# ProPrj_ESP32-S3.net
KiCad netlist of a schematic drawn in EasyEDA Pro
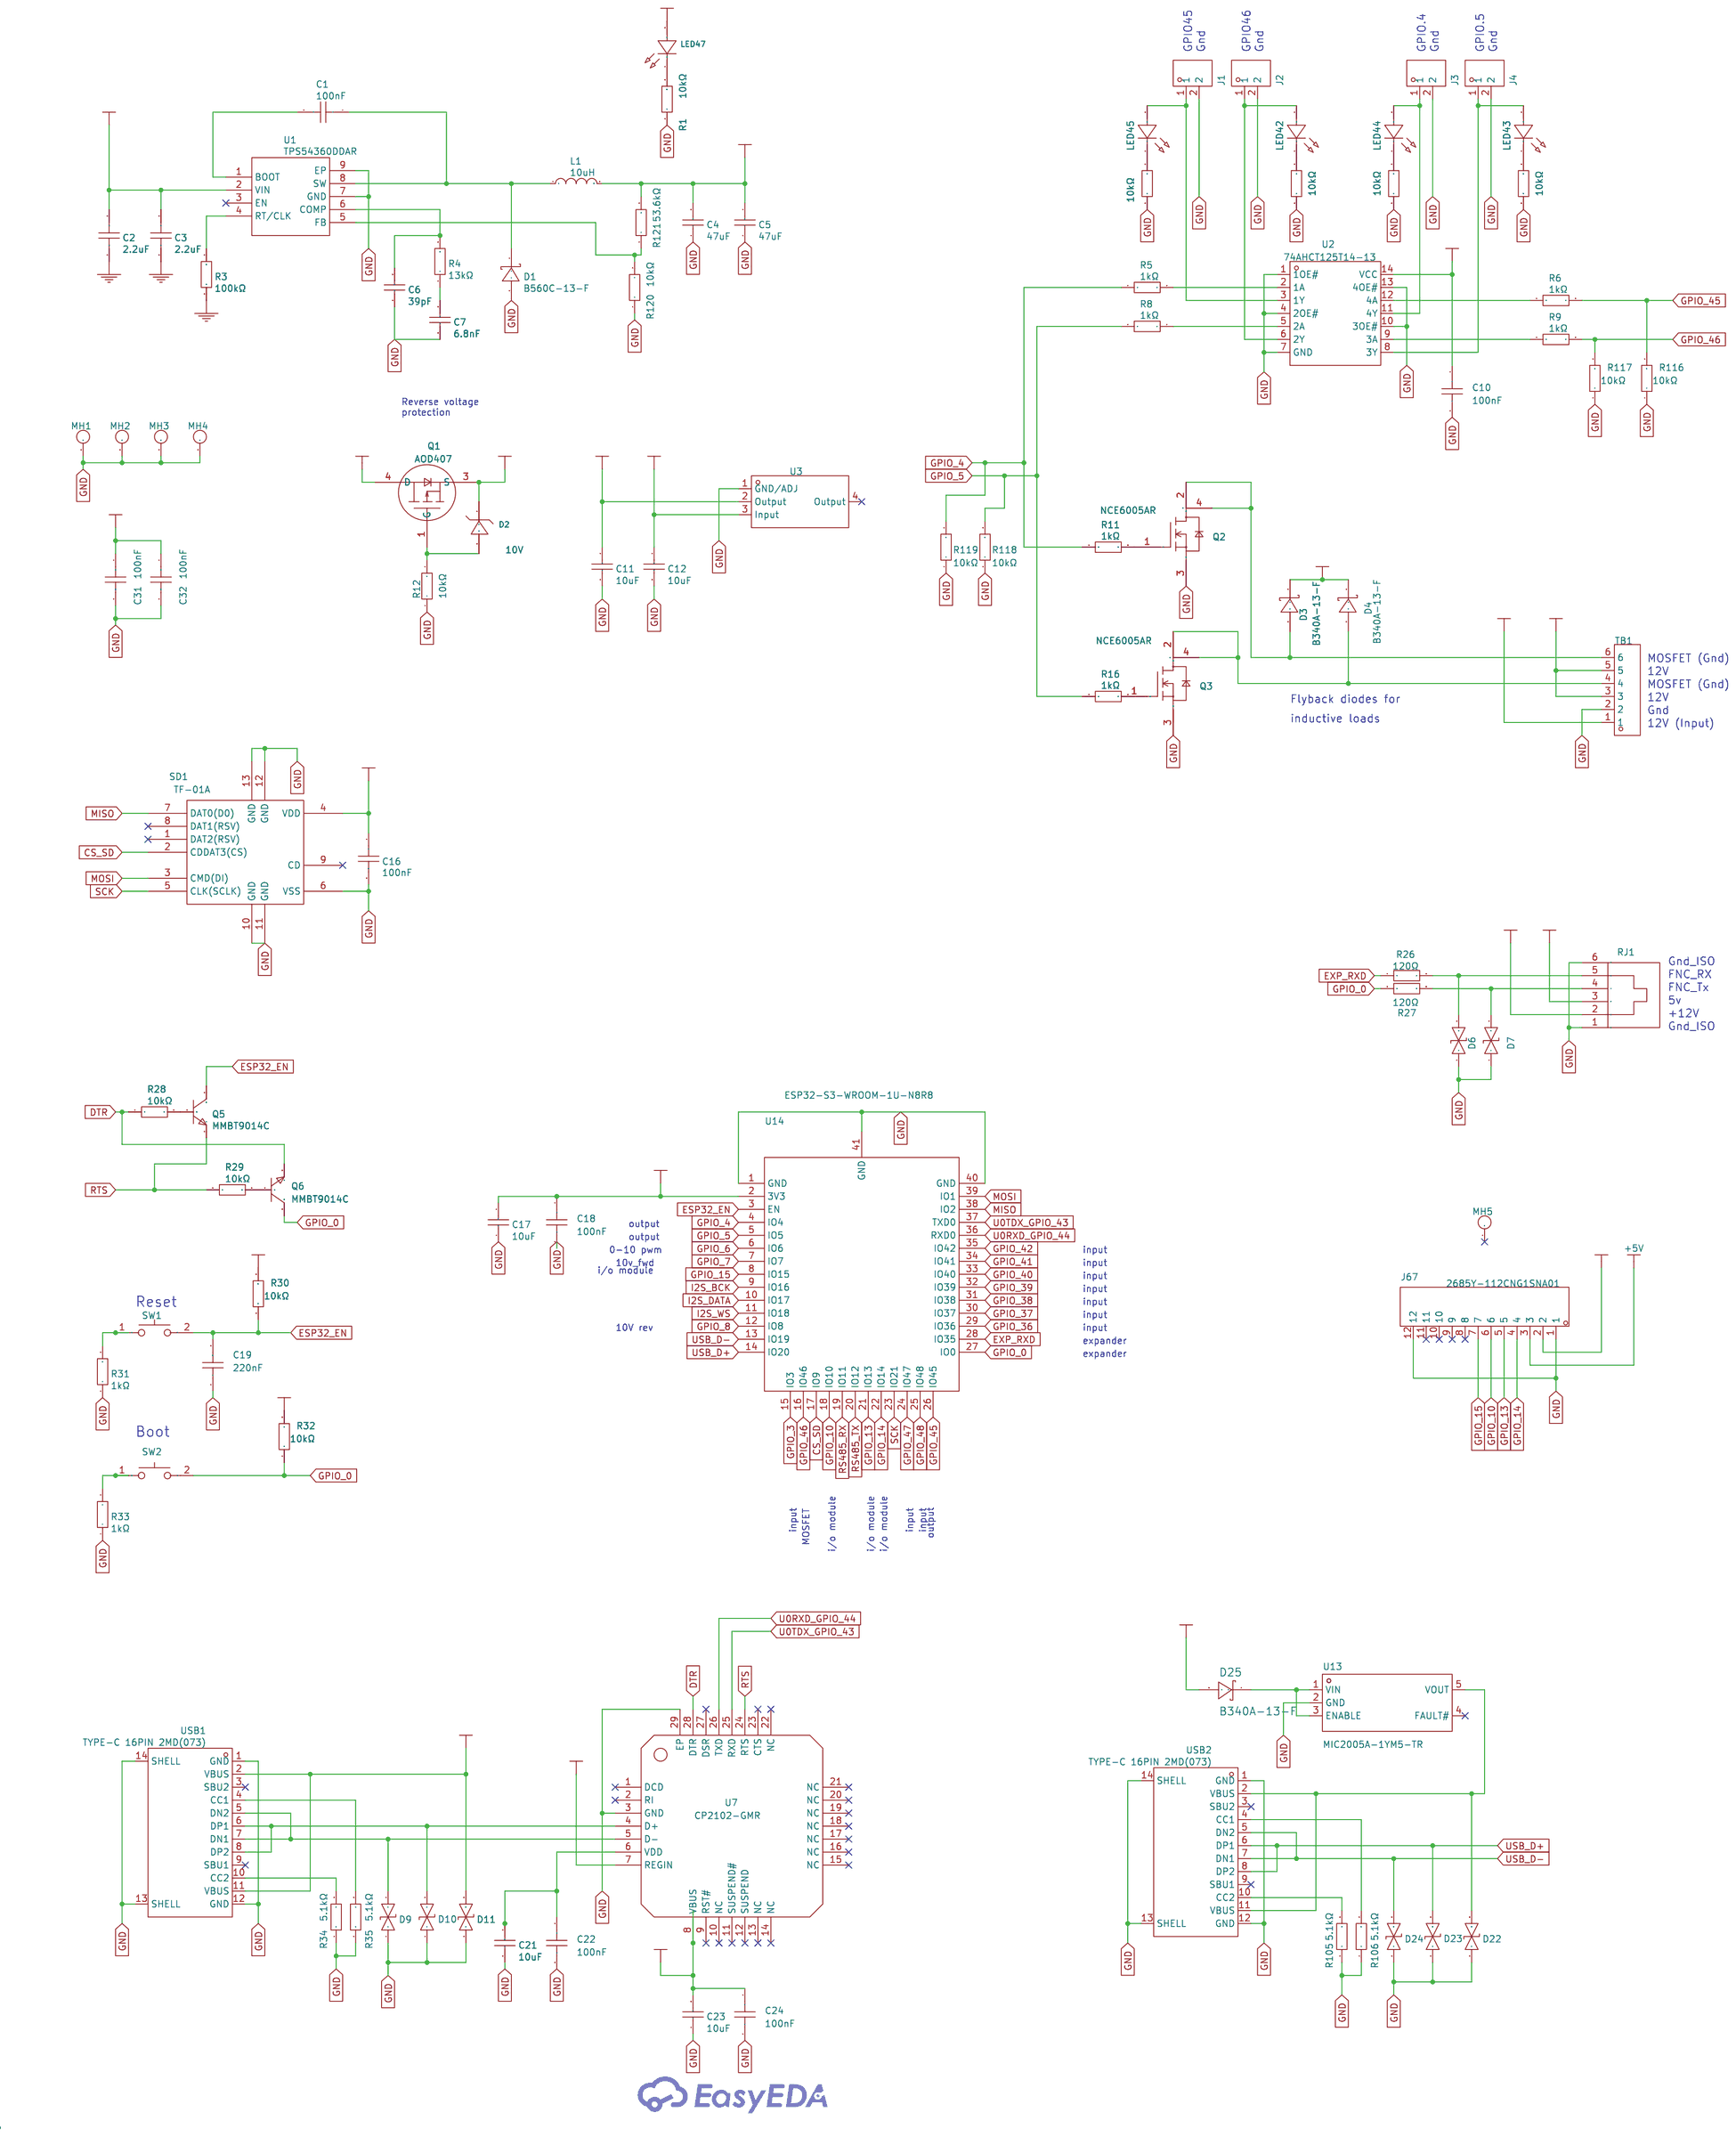
[diagram p0: P1]
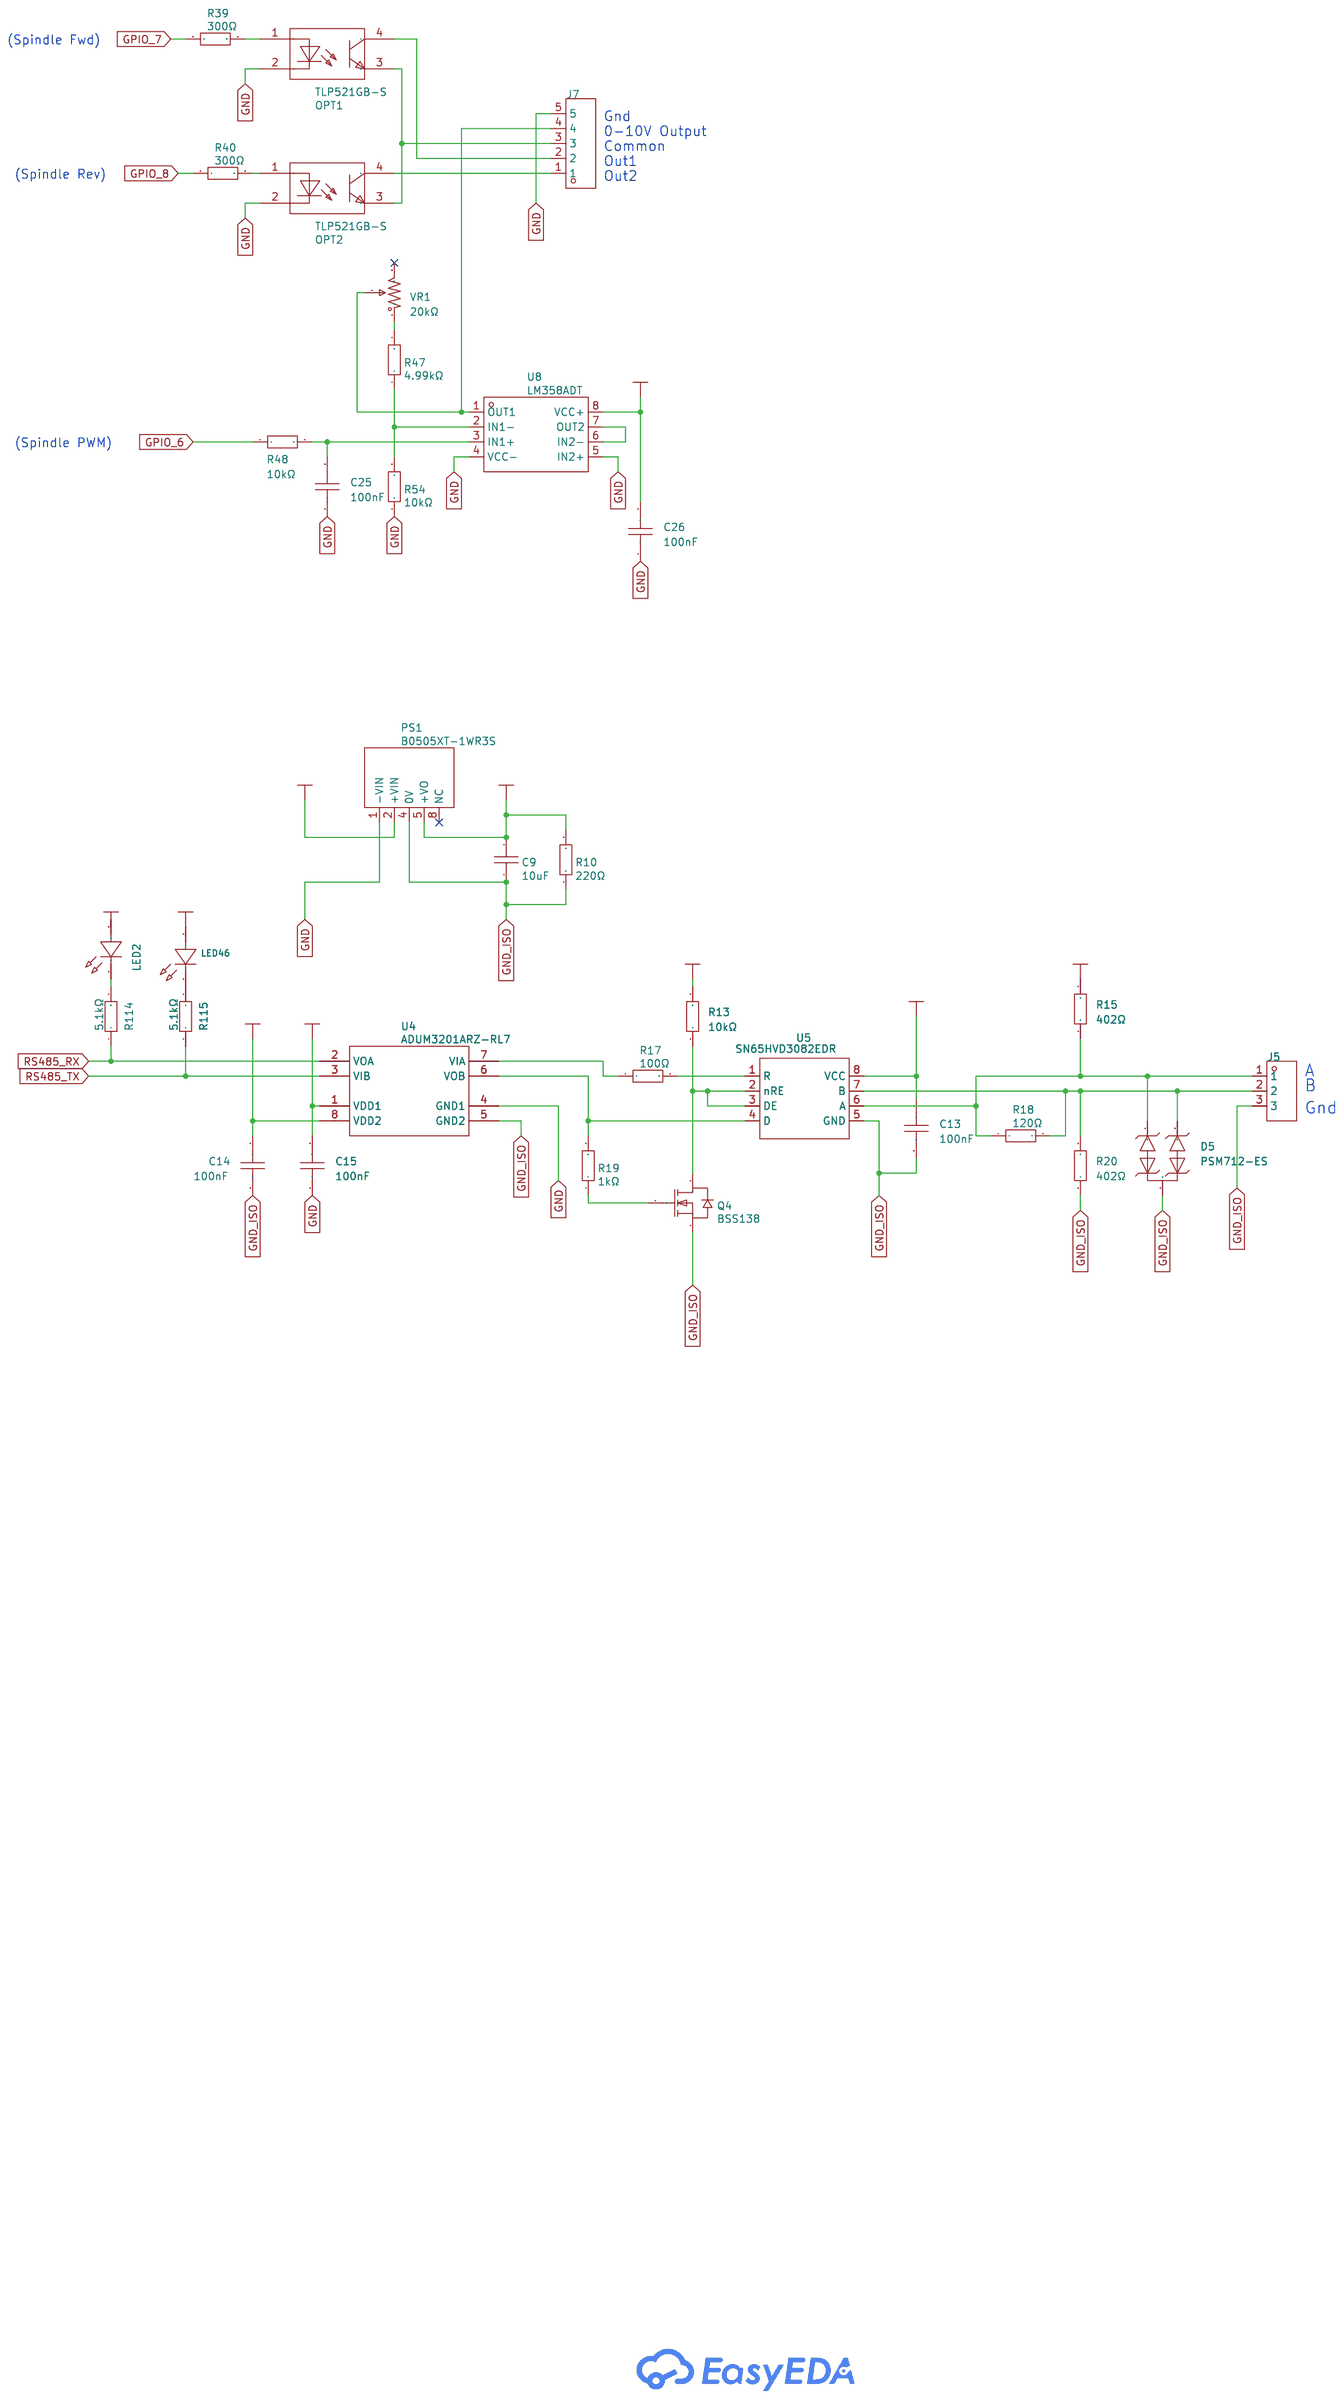
[diagram p1: P2]
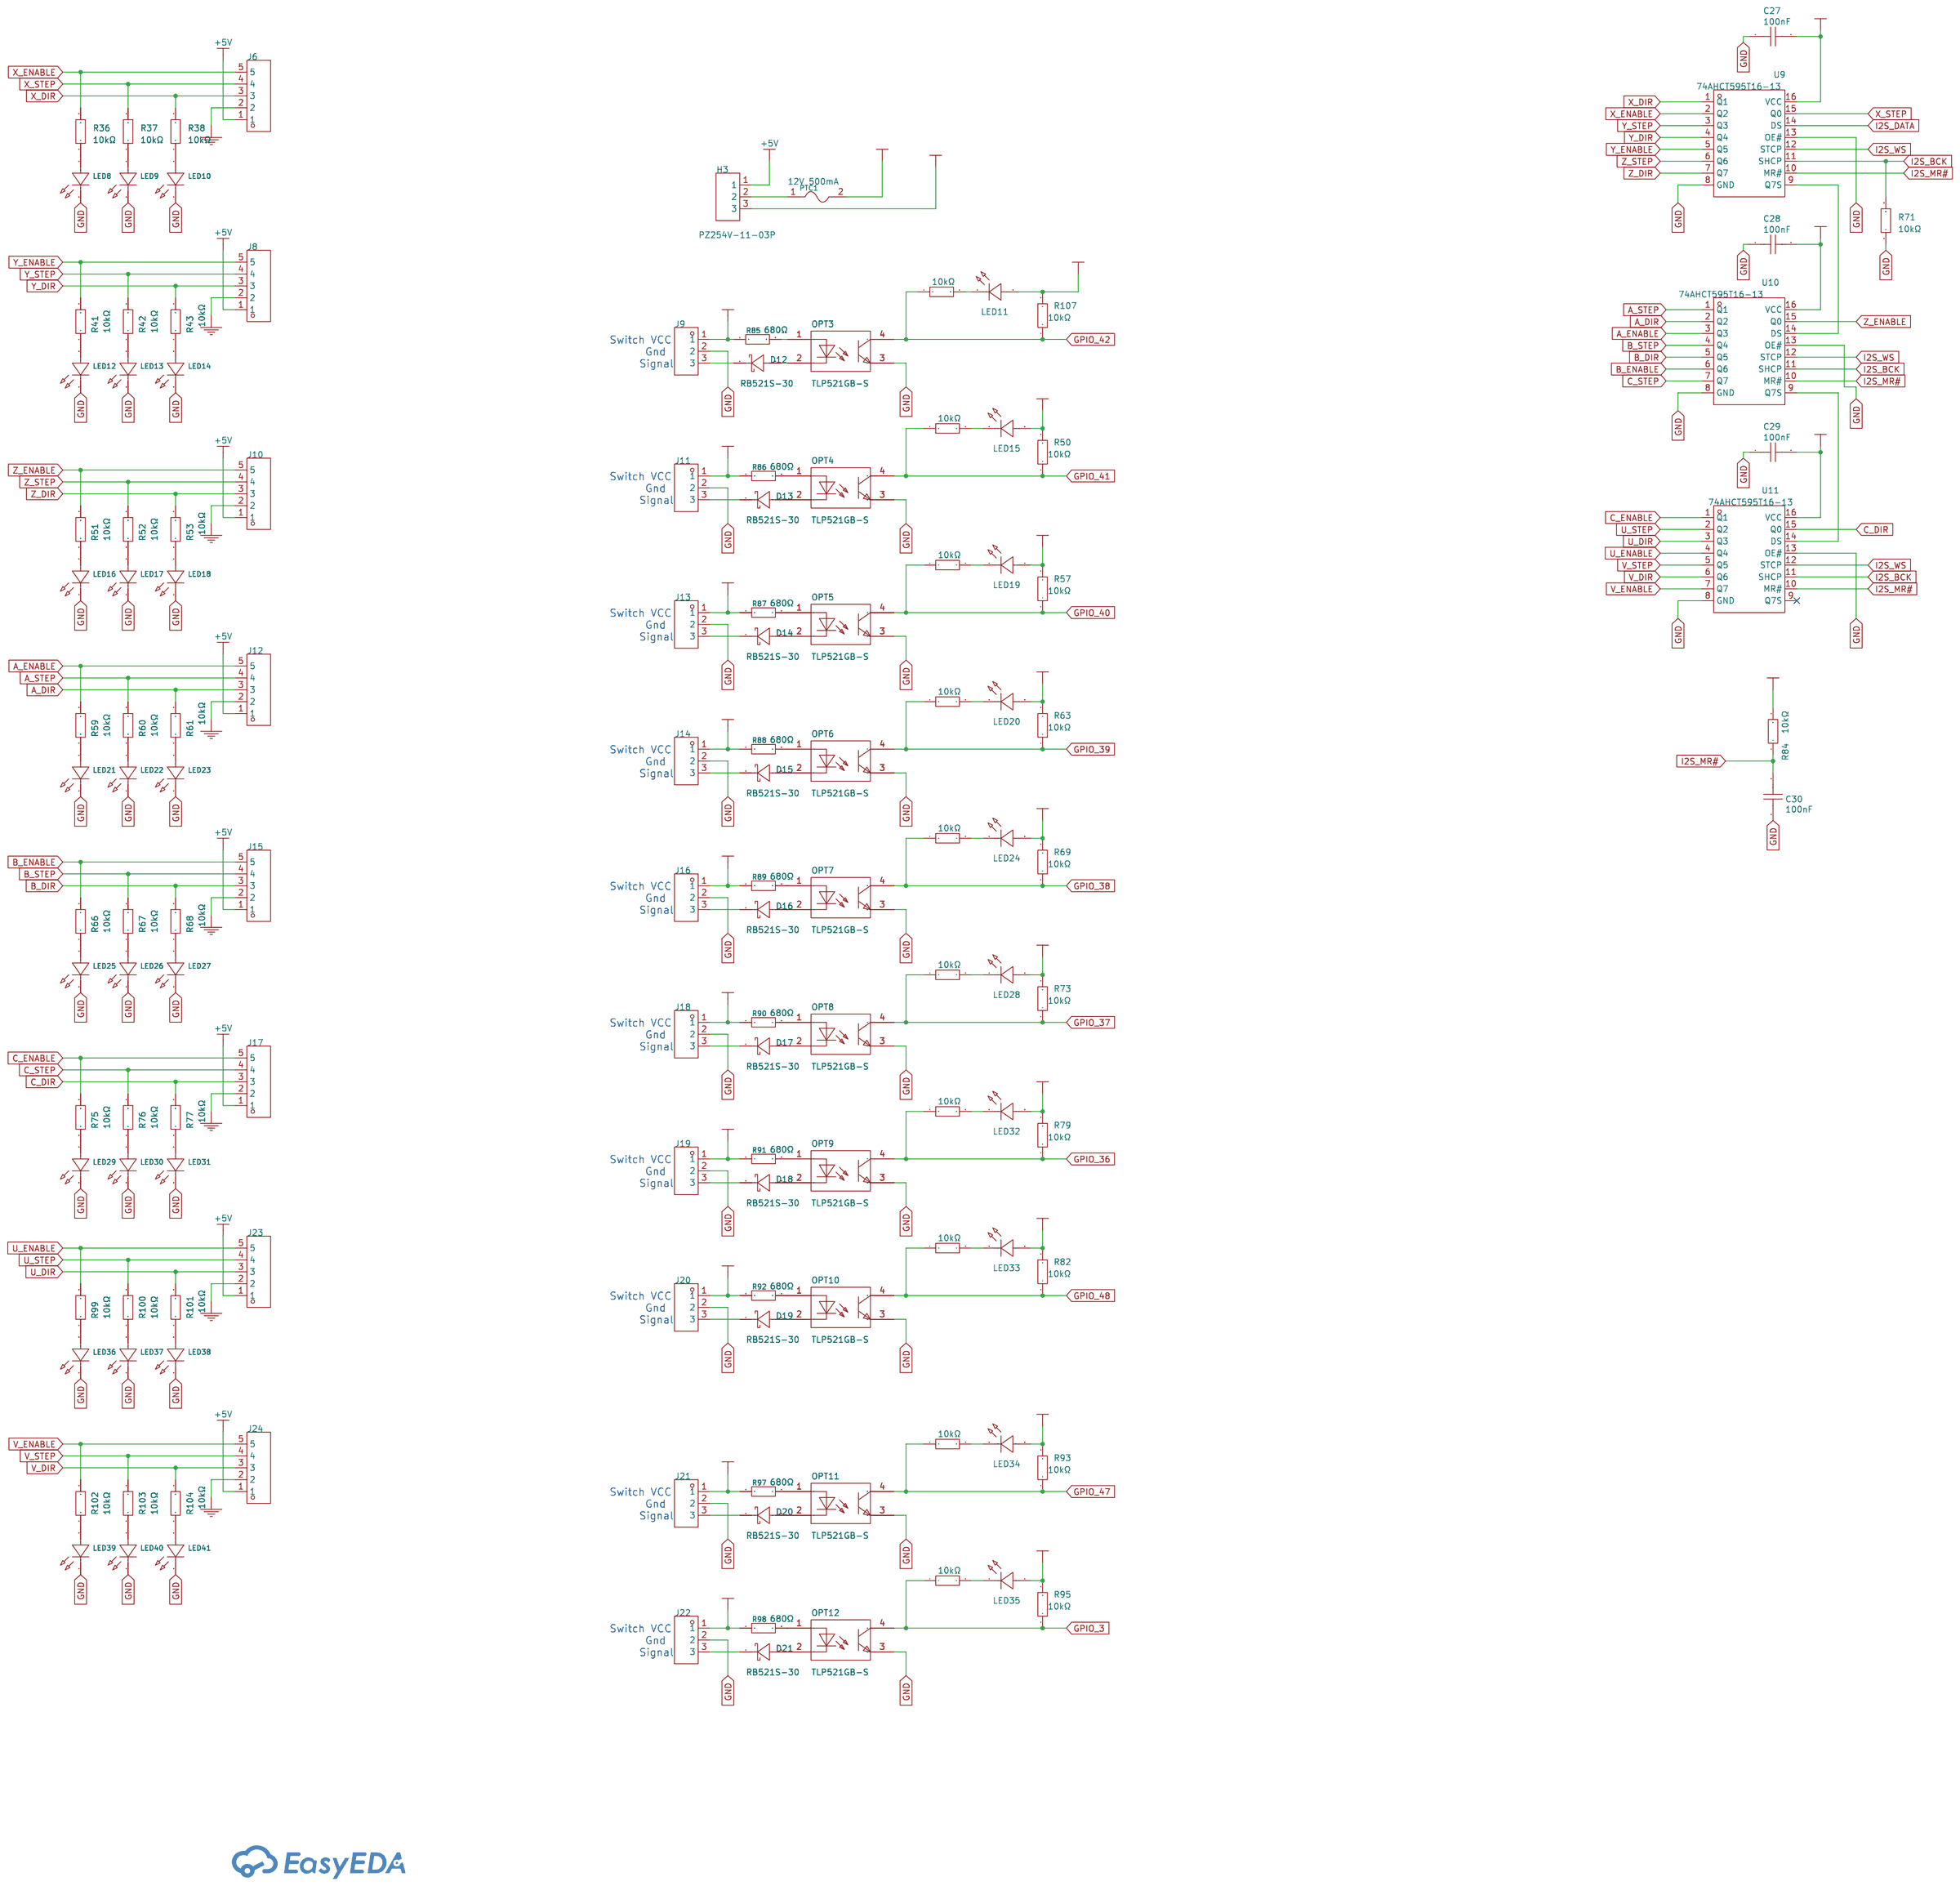
[diagram p2: P3]

(export (version "E")
  (design (tool "Eeschema 10.0.6"))
  (components
    (comp (ref "C1")
      (value "100nF")
      (footprint "easyedapro:C0402")
      (fields (field (name "Manufacturer Part") "GCM155R71C104KA55D") (field (name "Manufacturer") "MuRata"))
      (libsource (lib "easyedapro") (part "100nF"))
    )
    (comp (ref "C2")
      (value "2.2uF")
      (footprint "easyedapro:C0805")
      (fields
        (field (name "Manufacturer Part") "CS2012X5R225K500NRE")
        (field (name "Manufacturer") "SAMWHA(三和)")
      )
      (libsource (lib "easyedapro") (part "2.2uF"))
    )
    (comp (ref "C3")
      (value "2.2uF")
      (footprint "easyedapro:C0805")
      (fields
        (field (name "Manufacturer Part") "CS2012X5R225K500NRE")
        (field (name "Manufacturer") "SAMWHA(三和)")
      )
      (libsource (lib "easyedapro") (part "2.2uF"))
    )
    (comp (ref "C4")
      (value "47uF")
      (footprint "easyedapro:C0805")
      (fields (field (name "Manufacturer Part") "CL21A476MQYNNNE") (field (name "Manufacturer") "SAMSUNG"))
      (libsource (lib "easyedapro") (part "47uF"))
    )
    (comp (ref "C5")
      (value "47uF")
      (footprint "easyedapro:C0805")
      (fields (field (name "Manufacturer Part") "CL21A476MQYNNNE") (field (name "Manufacturer") "SAMSUNG"))
      (libsource (lib "easyedapro") (part "47uF"))
    )
    (comp (ref "C6")
      (value "39pF")
      (footprint "easyedapro:C0402")
      (fields (field (name "Manufacturer Part") "CC0402JRNPO9BN390") (field (name "Manufacturer") "YAGEO"))
      (libsource (lib "easyedapro") (part "39pF"))
    )
    (comp (ref "C7")
      (value "6.8nF")
      (footprint "easyedapro:C0402")
      (fields (field (name "Manufacturer Part") "0402B682K500NT") (field (name "Manufacturer") "FH"))
      (libsource (lib "easyedapro") (part "6.8nF"))
    )
    (comp (ref "C10")
      (value "100nF")
      (footprint "easyedapro:C0402")
      (fields (field (name "Manufacturer Part") "GCM155R71C104KA55D") (field (name "Manufacturer") "MuRata"))
      (libsource (lib "easyedapro") (part "100nF"))
    )
    (comp (ref "C11")
      (value "10uF")
      (footprint "easyedapro:C0805")
      (fields (field (name "Manufacturer Part") "CL21A106KAYNNNE") (field (name "Manufacturer") "SAMSUNG"))
      (libsource (lib "easyedapro") (part "10uF"))
    )
    (comp (ref "C12")
      (value "10uF")
      (footprint "easyedapro:C0805")
      (fields (field (name "Manufacturer Part") "CL21A106KAYNNNE") (field (name "Manufacturer") "SAMSUNG"))
      (libsource (lib "easyedapro") (part "10uF"))
    )
    (comp (ref "C16")
      (value "100nF")
      (footprint "easyedapro:C0402")
      (fields (field (name "Manufacturer Part") "GCM155R71C104KA55D") (field (name "Manufacturer") "MuRata"))
      (libsource (lib "easyedapro") (part "100nF"))
    )
    (comp (ref "C17")
      (value "10uF")
      (footprint "easyedapro:C0805")
      (fields (field (name "Manufacturer Part") "CL21A106KAYNNNE") (field (name "Manufacturer") "SAMSUNG"))
      (libsource (lib "easyedapro") (part "10uF"))
    )
    (comp (ref "C18")
      (value "100nF")
      (footprint "easyedapro:C0402")
      (fields (field (name "Manufacturer Part") "GCM155R71C104KA55D") (field (name "Manufacturer") "MuRata"))
      (libsource (lib "easyedapro") (part "100nF"))
    )
    (comp (ref "C19")
      (value "220nF")
      (footprint "easyedapro:C0402")
      (description "Capacitance:220nF Tolerance:±10% Tolerance:±10% Voltage Rating:16V Temperature Coefficient:X7R")
      (fields (field (name "Manufacturer Part") "0402B224K160NT") (field (name "Manufacturer") "FH(风华)"))
      (libsource (lib "easyedapro") (part "0402B224K160NT"))
    )
    (comp (ref "C21")
      (value "10uF")
      (footprint "easyedapro:C0805")
      (fields (field (name "Manufacturer Part") "CL21A106KAYNNNE") (field (name "Manufacturer") "SAMSUNG"))
      (libsource (lib "easyedapro") (part "10uF"))
    )
    (comp (ref "C22")
      (value "100nF")
      (footprint "easyedapro:C0402")
      (fields (field (name "Manufacturer Part") "GCM155R71C104KA55D") (field (name "Manufacturer") "MuRata"))
      (libsource (lib "easyedapro") (part "100nF"))
    )
    (comp (ref "C23")
      (value "10uF")
      (footprint "easyedapro:C0805")
      (fields (field (name "Manufacturer Part") "CL21A106KAYNNNE") (field (name "Manufacturer") "SAMSUNG"))
      (libsource (lib "easyedapro") (part "10uF"))
    )
    (comp (ref "C24")
      (value "100nF")
      (footprint "easyedapro:C0402")
      (fields (field (name "Manufacturer Part") "GCM155R71C104KA55D") (field (name "Manufacturer") "MuRata"))
      (libsource (lib "easyedapro") (part "100nF"))
    )
    (comp (ref "C31")
      (value "100nF")
      (footprint "easyedapro:C0402")
      (fields (field (name "Manufacturer Part") "GCM155R71C104KA55D") (field (name "Manufacturer") "MuRata"))
      (libsource (lib "easyedapro") (part "100nF"))
    )
    (comp (ref "C32")
      (value "100nF")
      (footprint "easyedapro:C0402")
      (fields (field (name "Manufacturer Part") "GCM155R71C104KA55D") (field (name "Manufacturer") "MuRata"))
      (libsource (lib "easyedapro") (part "100nF"))
    )
    (comp (ref "D1")
      (value "B560C-13-F")
      (footprint "easyedapro:SMC_L7.1-W6.2-LS8.1-RD")
      (fields (field (name "Manufacturer") "DIODES(美台)"))
      (libsource (lib "easyedapro") (part "B560C-13-F"))
    )
    (comp (ref "D2")
      (value "10V")
      (footprint "easyedapro:SOD-123_L2.8-W1.8-LS3.7-RD")
      (fields (field (name "Manufacturer Part") "BZT52C10") (field (name "Manufacturer") "MDD"))
      (libsource (lib "easyedapro") (part "BZT52C10_C173431"))
    )
    (comp (ref "D3")
      (value "B340A-13-F")
      (footprint "easyedapro:SMA_L4.4-W2.6-LS5.0-RD")
      (fields (field (name "Manufacturer") "DIODES(美台)"))
      (libsource (lib "easyedapro") (part "B340A-13-F"))
    )
    (comp (ref "D4")
      (value "B340A-13-F")
      (footprint "easyedapro:SMA_L4.4-W2.6-LS5.0-RD")
      (fields (field (name "Manufacturer") "DIODES(美台)"))
      (libsource (lib "easyedapro") (part "B340A-13-F"))
    )
    (comp (ref "D6")
      (value "SD03C_C502532")
      (footprint "easyedapro:SOD-323_L1.8-W1.3-LS2.5-BI")
      (fields
        (field (name "Manufacturer Part") "SD03C")
        (field (name "Manufacturer") "MDD")
        (field (name "Contributor") "LCSC")
      )
      (libsource (lib "easyedapro") (part "SD03C_C502532"))
    )
    (comp (ref "D7")
      (value "SD03C_C502532")
      (footprint "easyedapro:SOD-323_L1.8-W1.3-LS2.5-BI")
      (fields
        (field (name "Manufacturer Part") "SD03C")
        (field (name "Manufacturer") "MDD")
        (field (name "Contributor") "LCSC")
      )
      (libsource (lib "easyedapro") (part "SD03C_C502532"))
    )
    (comp (ref "D9")
      (value "LESD5D5.0CT1G")
      (footprint "easyedapro:SOD-523_L1.2-W0.8-LS1.6-BI")
      (fields (field (name "Manufacturer") "Leshan Radio"))
      (libsource (lib "easyedapro") (part "LESD5D5.0CT1G"))
    )
    (comp (ref "D10")
      (value "LESD5D5.0CT1G")
      (footprint "easyedapro:SOD-523_L1.2-W0.8-LS1.6-BI")
      (fields (field (name "Manufacturer") "Leshan Radio"))
      (libsource (lib "easyedapro") (part "LESD5D5.0CT1G"))
    )
    (comp (ref "D11")
      (value "LESD5D5.0CT1G")
      (footprint "easyedapro:SOD-523_L1.2-W0.8-LS1.6-BI")
      (fields (field (name "Manufacturer") "Leshan Radio"))
      (libsource (lib "easyedapro") (part "LESD5D5.0CT1G"))
    )
    (comp (ref "D22")
      (value "LESD5D5.0CT1G")
      (footprint "easyedapro:SOD-523_L1.2-W0.8-LS1.6-BI")
      (fields (field (name "Manufacturer") "Leshan Radio"))
      (libsource (lib "easyedapro") (part "LESD5D5.0CT1G"))
    )
    (comp (ref "D23")
      (value "LESD5D5.0CT1G")
      (footprint "easyedapro:SOD-523_L1.2-W0.8-LS1.6-BI")
      (fields (field (name "Manufacturer") "Leshan Radio"))
      (libsource (lib "easyedapro") (part "LESD5D5.0CT1G"))
    )
    (comp (ref "D24")
      (value "LESD5D5.0CT1G")
      (footprint "easyedapro:SOD-523_L1.2-W0.8-LS1.6-BI")
      (fields (field (name "Manufacturer") "Leshan Radio"))
      (libsource (lib "easyedapro") (part "LESD5D5.0CT1G"))
    )
    (comp (ref "D25")
      (value "B340A-13-F")
      (footprint "easyedapro:SMA_L4.4-W2.6-LS5.0-RD")
      (fields (field (name "Manufacturer") "DIODES(美台)"))
      (libsource (lib "easyedapro") (part "B340A-13-F"))
    )
    (comp (ref "J1")
      (value "ZX-XH2.54-2PZZ-R")
      (footprint "easyedapro:CONN-TH_XH2.54-2P")
      (fields (field (name "Manufacturer") "Megastar(兆星)"))
      (libsource (lib "easyedapro") (part "ZX-XH2.54-2PZZ-R"))
    )
    (comp (ref "J2")
      (value "ZX-XH2.54-2PZZ-R")
      (footprint "easyedapro:CONN-TH_XH2.54-2P")
      (fields (field (name "Manufacturer") "Megastar(兆星)"))
      (libsource (lib "easyedapro") (part "ZX-XH2.54-2PZZ-R"))
    )
    (comp (ref "J3")
      (value "ZX-XH2.54-2PZZ-R")
      (footprint "easyedapro:CONN-TH_XH2.54-2P")
      (fields (field (name "Manufacturer") "Megastar(兆星)"))
      (libsource (lib "easyedapro") (part "ZX-XH2.54-2PZZ-R"))
    )
    (comp (ref "J4")
      (value "ZX-XH2.54-2PZZ-R")
      (footprint "easyedapro:CONN-TH_XH2.54-2P")
      (fields (field (name "Manufacturer") "Megastar(兆星)"))
      (libsource (lib "easyedapro") (part "ZX-XH2.54-2PZZ-R"))
    )
    (comp (ref "J67")
      (value "2685Y-112CNG1SNA01")
      (footprint "easyedapro:HDR-TH_12P-P2.54-V-F")
      (fields (field (name "Manufacturer") "华宇创"))
      (libsource (lib "easyedapro") (part "2685Y-112CNG1SNA01"))
    )
    (comp (ref "L1")
      (value "10uH")
      (footprint "easyedapro:IND-SMD_L7.1-W6.6")
      (fields
        (field (name "Manufacturer Part") "PSPMAA0603-100M-ANF")
        (field (name "Manufacturer") "PROD(谱罗德)")
      )
      (libsource (lib "easyedapro") (part "10uH"))
    )
    (comp (ref "LED42")
      (value "XL-1608SURC-06")
      (footprint "easyedapro:LED0603-RD_RED")
      (fields (field (name "Manufacturer") "XINGLIGHT(成兴光)") (field (name "Contributor") "LCSC"))
      (libsource (lib "easyedapro") (part "XL-1608SURC-06"))
    )
    (comp (ref "LED43")
      (value "XL-1608SURC-06")
      (footprint "easyedapro:LED0603-RD_RED")
      (fields (field (name "Manufacturer") "XINGLIGHT(成兴光)") (field (name "Contributor") "LCSC"))
      (libsource (lib "easyedapro") (part "XL-1608SURC-06"))
    )
    (comp (ref "LED44")
      (value "XL-1608SURC-06")
      (footprint "easyedapro:LED0603-RD_RED")
      (fields (field (name "Manufacturer") "XINGLIGHT(成兴光)") (field (name "Contributor") "LCSC"))
      (libsource (lib "easyedapro") (part "XL-1608SURC-06"))
    )
    (comp (ref "LED45")
      (value "XL-1608SURC-06")
      (footprint "easyedapro:LED0603-RD_RED")
      (fields (field (name "Manufacturer") "XINGLIGHT(成兴光)") (field (name "Contributor") "LCSC"))
      (libsource (lib "easyedapro") (part "XL-1608SURC-06"))
    )
    (comp (ref "LED47")
      (value "XL-1608UGC-04")
      (footprint "easyedapro:LED0603-RD_GREEN")
      (fields (field (name "Manufacturer") "XINGLIGHT(成兴光)"))
      (libsource (lib "easyedapro") (part "XL-1608UGC-04"))
    )
    (comp (ref "MH1")
      (value "Mounting Hole 3.5")
      (footprint "easyedapro:MOUNTING HOLE 3.5")
      (libsource (lib "easyedapro") (part "Mounting Hole 3.5"))
    )
    (comp (ref "MH2")
      (value "Mounting Hole 3.5")
      (footprint "easyedapro:MOUNTING HOLE 3.5")
      (libsource (lib "easyedapro") (part "Mounting Hole 3.5"))
    )
    (comp (ref "MH3")
      (value "Mounting Hole 3.5")
      (footprint "easyedapro:MOUNTING HOLE 3.5")
      (libsource (lib "easyedapro") (part "Mounting Hole 3.5"))
    )
    (comp (ref "MH4")
      (value "Mounting Hole 3.5")
      (footprint "easyedapro:MOUNTING HOLE 3.5")
      (libsource (lib "easyedapro") (part "Mounting Hole 3.5"))
    )
    (comp (ref "MH5")
      (value "Mounting Hole 3.5")
      (footprint "easyedapro:MOUNTING HOLE 3.5")
      (libsource (lib "easyedapro") (part "Mounting Hole 3.5"))
    )
    (comp (ref "Q1")
      (value "AOD407")
      (footprint "easyedapro:TO-252-2_L6.5-W6.1-P4.58-LS10.0-TL")
      (fields (field (name "Manufacturer") "AOS"))
      (libsource (lib "easyedapro") (part "AOD407"))
    )
    (comp (ref "Q2")
      (value "NCE6005AR")
      (footprint "easyedapro:SOT-223_L6.5-W3.5-P2.30-LS7.0-BR")
      (fields (field (name "Manufacturer") "Wuxi NCE Power Semiconductor"))
      (libsource (lib "easyedapro") (part "NCE6005AR"))
    )
    (comp (ref "Q3")
      (value "NCE6005AR")
      (footprint "easyedapro:SOT-223_L6.5-W3.5-P2.30-LS7.0-BR")
      (fields (field (name "Manufacturer") "Wuxi NCE Power Semiconductor"))
      (libsource (lib "easyedapro") (part "NCE6005AR"))
    )
    (comp (ref "Q5")
      (value "MMBT9014C")
      (footprint "easyedapro:SOT-23-3_L2.9-W1.3-P1.90-LS2.4-BR")
      (fields (field (name "Manufacturer") "SEMTECH"))
      (libsource (lib "easyedapro") (part "MMBT9014C"))
    )
    (comp (ref "Q6")
      (value "MMBT9014C")
      (footprint "easyedapro:SOT-23-3_L2.9-W1.3-P1.90-LS2.4-BR")
      (fields (field (name "Manufacturer") "SEMTECH"))
      (libsource (lib "easyedapro") (part "MMBT9014C"))
    )
    (comp (ref "R1") (value "10kΩ") (libsource (lib "easyedapro") (part "10kΩ")))
    (comp (ref "R3")
      (value "100kΩ")
      (footprint "easyedapro:R0402")
      (fields (field (name "Manufacturer Part") "0402WGF1003TCE") (field (name "Manufacturer") "UniOhm"))
      (libsource (lib "easyedapro") (part "100kΩ"))
    )
    (comp (ref "R4")
      (value "13kΩ")
      (footprint "easyedapro:R0402")
      (fields (field (name "Manufacturer Part") "0402WGF1302TCE") (field (name "Manufacturer") "UniOhm"))
      (libsource (lib "easyedapro") (part "13kΩ"))
    )
    (comp (ref "R5") (value "1kΩ") (libsource (lib "easyedapro") (part "1kΩ")))
    (comp (ref "R6") (value "1kΩ") (libsource (lib "easyedapro") (part "1kΩ")))
    (comp (ref "R8") (value "1kΩ") (libsource (lib "easyedapro") (part "1kΩ")))
    (comp (ref "R9") (value "1kΩ") (libsource (lib "easyedapro") (part "1kΩ")))
    (comp (ref "R11") (value "1kΩ") (libsource (lib "easyedapro") (part "1kΩ")))
    (comp (ref "R12") (value "10kΩ") (libsource (lib "easyedapro") (part "10kΩ")))
    (comp (ref "R16") (value "1kΩ") (libsource (lib "easyedapro") (part "1kΩ")))
    (comp (ref "R26") (value "120Ω") (libsource (lib "easyedapro") (part "120Ω")))
    (comp (ref "R27") (value "120Ω") (libsource (lib "easyedapro") (part "120Ω")))
    (comp (ref "R28") (value "10kΩ") (libsource (lib "") (part "10kΩ_1")))
    (comp (ref "R29") (value "10kΩ") (libsource (lib "") (part "10kΩ_1")))
    (comp (ref "R30") (value "10kΩ") (libsource (lib "") (part "10kΩ_2")))
    (comp (ref "R31") (value "1kΩ") (libsource (lib "easyedapro") (part "1kΩ")))
    (comp (ref "R32") (value "10kΩ") (libsource (lib "") (part "10kΩ_2")))
    (comp (ref "R33") (value "1kΩ") (libsource (lib "easyedapro") (part "1kΩ")))
    (comp (ref "R34")
      (value "5.1kΩ")
      (footprint "easyedapro:R0402")
      (fields (field (name "Manufacturer Part") "0402WGF5101TCE") (field (name "Manufacturer") "UniOhm"))
      (libsource (lib "easyedapro") (part "5.1kΩ"))
    )
    (comp (ref "R35")
      (value "5.1kΩ")
      (footprint "easyedapro:R0402")
      (fields (field (name "Manufacturer Part") "0402WGF5101TCE") (field (name "Manufacturer") "UniOhm"))
      (libsource (lib "easyedapro") (part "5.1kΩ"))
    )
    (comp (ref "R105")
      (value "5.1kΩ")
      (footprint "easyedapro:R0402")
      (fields (field (name "Manufacturer Part") "0402WGF5101TCE") (field (name "Manufacturer") "UniOhm"))
      (libsource (lib "easyedapro") (part "5.1kΩ"))
    )
    (comp (ref "R106")
      (value "5.1kΩ")
      (footprint "easyedapro:R0402")
      (fields (field (name "Manufacturer Part") "0402WGF5101TCE") (field (name "Manufacturer") "UniOhm"))
      (libsource (lib "easyedapro") (part "5.1kΩ"))
    )
    (comp (ref "R110") (value "10kΩ") (libsource (lib "easyedapro") (part "10kΩ")))
    (comp (ref "R111") (value "10kΩ") (libsource (lib "easyedapro") (part "10kΩ")))
    (comp (ref "R112") (value "10kΩ") (libsource (lib "easyedapro") (part "10kΩ")))
    (comp (ref "R113") (value "10kΩ") (libsource (lib "easyedapro") (part "10kΩ")))
    (comp (ref "R116") (value "10kΩ") (libsource (lib "") (part "10kΩ_2")))
    (comp (ref "R117") (value "10kΩ") (libsource (lib "") (part "10kΩ_2")))
    (comp (ref "R118") (value "10kΩ") (libsource (lib "") (part "10kΩ_2")))
    (comp (ref "R119") (value "10kΩ") (libsource (lib "") (part "10kΩ_2")))
    (comp (ref "R120") (value "10kΩ") (libsource (lib "easyedapro") (part "10kΩ")))
    (comp (ref "R121")
      (value "53.6kΩ")
      (footprint "easyedapro:R0402")
      (fields
        (field (name "Manufacturer Part") "0402WGF5362TCE")
        (field (name "Manufacturer") "UNI-ROYAL(厚声)")
      )
      (libsource (lib "easyedapro") (part "0402WGF5362TCE"))
    )
    (comp (ref "RJ1")
      (value "RJ1")
      (footprint "easyedapro:RJ11-TH_PCB-6P6C-90")
      (fields
        (field (name "Manufacturer Part") "R-RJ11R06P-A800")
        (field (name "Manufacturer") "Ckmtw(灿科盟)")
        (field (name "Contributor") "LCSC")
      )
      (libsource (lib "easyedapro") (part "RJ1"))
    )
    (comp (ref "SD1")
      (value "TF-01A")
      (footprint "easyedapro:TF-SMD_TF-01A")
      (fields (field (name "Manufacturer") "韩国韩荣"))
      (libsource (lib "easyedapro") (part "TF-01A"))
    )
    (comp (ref "SW1")
      (value "SKRKAEE020")
      (footprint "easyedapro:KEY-SMD_L3.9-W3.0-LS5.0")
      (fields (field (name "Manufacturer") "ALPS"))
      (libsource (lib "easyedapro") (part "SKRKAEE020"))
    )
    (comp (ref "SW2")
      (value "SKRKAEE020")
      (footprint "easyedapro:KEY-SMD_L3.9-W3.0-LS5.0")
      (fields (field (name "Manufacturer") "ALPS"))
      (libsource (lib "easyedapro") (part "SKRKAEE020"))
    )
    (comp (ref "TB1")
      (value "DB125-3.5-6P-GN-S")
      (footprint "easyedapro:CONN-TH_6P-P3.50_DB125-3.5-6P-GN-S")
      (fields (field (name "Manufacturer") "DORABO(地博电气)"))
      (libsource (lib "easyedapro") (part "DB125-3.5-6P-GN-S"))
    )
    (comp (ref "U1")
      (value "TPS54360DDAR")
      (footprint "easyedapro:SOIC-8_L5.0-W4.0-P1.27-LS6.0-BL-EP2.0")
      (fields (field (name "Manufacturer") "TI(德州仪器)"))
      (libsource (lib "easyedapro") (part "TPS54360DDAR"))
    )
    (comp (ref "U2")
      (value "74AHCT125T14-13")
      (footprint "easyedapro:TSSOP-14_L5.0-W4.4-P0.65-LS6.4-BL")
      (fields (field (name "Manufacturer") "DIODES(美台)"))
      (libsource (lib "easyedapro") (part "74AHCT125T14-13"))
    )
    (comp (ref "U3")
      (value "AMS1117-3.3_C369933")
      (footprint "easyedapro:SOT-223-4_L6.5-W3.5-P2.30-LS7.0-BR")
      (fields (field (name "Manufacturer Part") "AMS1117-3.3") (field (name "Manufacturer") "KEXIN"))
      (libsource (lib "easyedapro") (part "AMS1117-3.3_C369933"))
    )
    (comp (ref "U7")
      (value "CP2102-GMR")
      (footprint "easyedapro:WQFN-28_L5.0-W5.0-P0.50-BL-EP3.2")
      (fields (field (name "Manufacturer") "SILICON LABS"))
      (libsource (lib "easyedapro") (part "CP2102-GMR"))
    )
    (comp (ref "U13")
      (value "MIC2005A-1YM5-TR")
      (footprint "easyedapro:SOT-23-5_L3.0-W1.7-P0.95-LS2.8-BL")
      (fields (field (name "Manufacturer") "MICROCHIP(美国微芯)"))
      (libsource (lib "easyedapro") (part "MIC2005A-1YM5-TR"))
    )
    (comp (ref "U14")
      (value "ESP32-S3-WROOM-1U-N8R8")
      (footprint "easyedapro:WIRELM-SMD_ESP32-S3-WROOM-1U")
      (fields (field (name "Manufacturer") "ESPRESSIF(乐鑫)"))
      (libsource (lib "easyedapro") (part "ESP32-S3-WROOM-1U-N8R8"))
    )
    (comp (ref "USB1")
      (value "TYPE-C 16PIN 2MD(073)")
      (footprint "easyedapro:USB-C-SMD_TYPE-C-6PIN-2MD-073")
      (fields (field (name "Manufacturer") "SHOU HAN(首韩)"))
      (libsource (lib "easyedapro") (part "TYPE-C 16PIN 2MD(073)"))
    )
    (comp (ref "USB2")
      (value "TYPE-C 16PIN 2MD(073)")
      (footprint "easyedapro:USB-C-SMD_TYPE-C-6PIN-2MD-073")
      (fields (field (name "Manufacturer") "SHOU HAN(首韩)"))
      (libsource (lib "easyedapro") (part "TYPE-C 16PIN 2MD(073)"))
    )
    (comp (ref "C9")
      (value "10uF")
      (footprint "easyedapro:C0805")
      (fields
        (field (name "Manufacturer Part") "CL21A106KAYNNNE")
        (field (name "Manufacturer") "SAMSUNG(三星)")
      )
      (libsource (lib "easyedapro") (part "10uF"))
    )
    (comp (ref "C13")
      (value "100nF")
      (footprint "easyedapro:C0402")
      (fields (field (name "Manufacturer Part") "GCM155R71C104KA55D") (field (name "Manufacturer") "MuRata"))
      (libsource (lib "easyedapro") (part "100nF"))
    )
    (comp (ref "C14")
      (value "100nF")
      (footprint "easyedapro:C0402")
      (fields (field (name "Manufacturer Part") "GCM155R71C104KA55D") (field (name "Manufacturer") "MuRata"))
      (libsource (lib "easyedapro") (part "100nF"))
    )
    (comp (ref "C15")
      (value "100nF")
      (footprint "easyedapro:C0402")
      (fields (field (name "Manufacturer Part") "GCM155R71C104KA55D") (field (name "Manufacturer") "MuRata"))
      (libsource (lib "easyedapro") (part "100nF"))
    )
    (comp (ref "C25")
      (value "100nF")
      (footprint "easyedapro:C0402")
      (fields (field (name "Manufacturer Part") "GCM155R71C104KA55D") (field (name "Manufacturer") "MuRata"))
      (libsource (lib "easyedapro") (part "100nF"))
    )
    (comp (ref "C26")
      (value "100nF")
      (footprint "easyedapro:C0402")
      (fields (field (name "Manufacturer Part") "GCM155R71C104KA55D") (field (name "Manufacturer") "MuRata"))
      (libsource (lib "easyedapro") (part "100nF"))
    )
    (comp (ref "D5")
      (value "PSM712-ES")
      (footprint "easyedapro:SOT-23-3_L2.9-W1.3-P1.90-LS2.4-BR")
      (fields (field (name "Manufacturer") "ElecSuper(静芯微)"))
      (libsource (lib "easyedapro") (part "PSM712-ES"))
    )
    (comp (ref "J5")
      (value "ZX-XH2.54-3PZZ")
      (footprint "easyedapro:CONN-TH_3P-P2.54_2501S-3P")
      (fields (field (name "Manufacturer") "Megastar(兆星)"))
      (libsource (lib "easyedapro") (part "ZX-XH2.54-3PZZ"))
    )
    (comp (ref "J7")
      (value "B5B-XH-A-M(LF)(SN)")
      (footprint "easyedapro:CONN-TH_5P-P2.50_JST_B5B-XH-A-M")
      (fields (field (name "Manufacturer") "JST"))
      (libsource (lib "easyedapro") (part "B5B-XH-A-M(LF)(SN)"))
    )
    (comp (ref "LED2")
      (value "XL-1608SURC-06")
      (footprint "easyedapro:LED0603-RD_RED")
      (fields (field (name "Manufacturer") "XINGLIGHT(成兴光)") (field (name "Contributor") "LCSC"))
      (libsource (lib "easyedapro") (part "XL-1608SURC-06"))
    )
    (comp (ref "LED46")
      (value "XL-1608UGC-04")
      (footprint "easyedapro:LED0603-RD_GREEN")
      (fields (field (name "Manufacturer") "XINGLIGHT(成兴光)"))
      (libsource (lib "easyedapro") (part "XL-1608UGC-04"))
    )
    (comp (ref "OPT1")
      (value "TLP521GB-S")
      (footprint "easyedapro:OPTO-SMD-4_L6.5-W4.6-P2.54-LS10.0-TL")
      (fields (field (name "Manufacturer") "UMW(广东友台半导体)"))
      (libsource (lib "easyedapro") (part "TLP521GB-S"))
    )
    (comp (ref "OPT2")
      (value "TLP521GB-S")
      (footprint "easyedapro:OPTO-SMD-4_L6.5-W4.6-P2.54-LS10.0-TL")
      (fields (field (name "Manufacturer") "UMW(广东友台半导体)"))
      (libsource (lib "easyedapro") (part "TLP521GB-S"))
    )
    (comp (ref "PS1")
      (value "B0505XT-1WR3S")
      (footprint "easyedapro:PWRM-SMD_B0505XT-1WR3S")
      (fields (field (name "Manufacturer") "rlt") (field (name "Contributor") "LCSC"))
      (libsource (lib "easyedapro") (part "B0505XT-1WR3S"))
    )
    (comp (ref "Q4")
      (value "BSS138")
      (footprint "easyedapro:SOT-23-3_L2.9-W1.3-P1.90-LS2.4-BR")
      (fields (field (name "Manufacturer") "CJ(江苏长电/长晶)"))
      (libsource (lib "easyedapro") (part "BSS138"))
    )
    (comp (ref "R10") (value "220Ω") (libsource (lib "easyedapro") (part "220Ω")))
    (comp (ref "R13") (value "10kΩ") (libsource (lib "easyedapro") (part "10kΩ")))
    (comp (ref "R15")
      (value "402Ω")
      (footprint "easyedapro:R0402")
      (fields (field (name "Manufacturer Part") "RC0402FR-07402RL") (field (name "Manufacturer") "YAGEO(国巨)"))
      (libsource (lib "easyedapro") (part "RC0402FR-07402RL"))
    )
    (comp (ref "R17") (value "100Ω") (libsource (lib "easyedapro") (part "100Ω")))
    (comp (ref "R18") (value "120Ω") (libsource (lib "easyedapro") (part "120Ω")))
    (comp (ref "R19") (value "1kΩ") (libsource (lib "easyedapro") (part "1kΩ")))
    (comp (ref "R20")
      (value "402Ω")
      (footprint "easyedapro:R0402")
      (fields (field (name "Manufacturer Part") "RC0402FR-07402RL") (field (name "Manufacturer") "YAGEO(国巨)"))
      (libsource (lib "easyedapro") (part "RC0402FR-07402RL"))
    )
    (comp (ref "R39") (value "300Ω") (libsource (lib "easyedapro") (part "300Ω")))
    (comp (ref "R40") (value "300Ω") (libsource (lib "easyedapro") (part "300Ω")))
    (comp (ref "R47") (value "4.99kΩ") (libsource (lib "easyedapro") (part "4.99kΩ")))
    (comp (ref "R48") (value "10kΩ") (libsource (lib "easyedapro") (part "10kΩ")))
    (comp (ref "R54") (value "10kΩ") (libsource (lib "easyedapro") (part "10kΩ")))
    (comp (ref "R114")
      (value "5.1kΩ")
      (footprint "easyedapro:R0402")
      (fields (field (name "Manufacturer Part") "0402WGF5101TCE") (field (name "Manufacturer") "UniOhm"))
      (libsource (lib "easyedapro") (part "5.1kΩ"))
    )
    (comp (ref "R115")
      (value "5.1kΩ")
      (footprint "easyedapro:R0402")
      (fields (field (name "Manufacturer Part") "0402WGF5101TCE") (field (name "Manufacturer") "UniOhm"))
      (libsource (lib "easyedapro") (part "5.1kΩ"))
    )
    (comp (ref "U4")
      (value "ADUM3201ARZ-RL7")
      (footprint "easyedapro:SOIC-8_L5.0-W4.0-P1.27-LS6.0-BL")
      (fields (field (name "Manufacturer") "ADI(亚德诺)/LINEAR(凌特)"))
      (libsource (lib "easyedapro") (part "ADUM3201ARZ-RL7"))
    )
    (comp (ref "U5")
      (value "SN65HVD3082EDR")
      (footprint "easyedapro:SOIC-8_L5.0-W4.0-P1.27-LS6.0-BL")
      (fields (field (name "Manufacturer") "TI(德州仪器)"))
      (libsource (lib "easyedapro") (part "SN65HVD3082EDR"))
    )
    (comp (ref "U8")
      (value "LM358ADT")
      (footprint "easyedapro:SOIC-8_L4.9-W3.9-P1.27-LS6.0-BL")
      (fields (field (name "Manufacturer") "STMicroelectronics"))
      (libsource (lib "easyedapro") (part "LM358ADT"))
    )
    (comp (ref "VR1")
      (value "20kΩ")
      (footprint "easyedapro:RES-ADJ-SMD_TC33X-2-104E")
      (fields (field (name "Manufacturer Part") "TC33X-2-203E") (field (name "Manufacturer") "BOURNS"))
      (libsource (lib "easyedapro") (part "TC33X-2-203E"))
    )
    (comp (ref "C27")
      (value "100nF")
      (footprint "easyedapro:C0402")
      (fields (field (name "Manufacturer Part") "GCM155R71C104KA55D") (field (name "Manufacturer") "MuRata"))
      (libsource (lib "easyedapro") (part "100nF"))
    )
    (comp (ref "C28")
      (value "100nF")
      (footprint "easyedapro:C0402")
      (fields (field (name "Manufacturer Part") "GCM155R71C104KA55D") (field (name "Manufacturer") "MuRata"))
      (libsource (lib "easyedapro") (part "100nF"))
    )
    (comp (ref "C29")
      (value "100nF")
      (footprint "easyedapro:C0402")
      (fields (field (name "Manufacturer Part") "GCM155R71C104KA55D") (field (name "Manufacturer") "MuRata"))
      (libsource (lib "easyedapro") (part "100nF"))
    )
    (comp (ref "C30")
      (value "100nF")
      (footprint "easyedapro:C0402")
      (fields (field (name "Manufacturer Part") "GCM155R71C104KA55D") (field (name "Manufacturer") "MuRata"))
      (libsource (lib "easyedapro") (part "100nF"))
    )
    (comp (ref "D12")
      (value "RB521S-30")
      (footprint "easyedapro:SOD-523_L1.2-W0.8-LS1.6-RD")
      (fields (field (name "Manufacturer") "TWGMC(台湾迪嘉)"))
      (libsource (lib "easyedapro") (part "RB521S-30_C727120"))
    )
    (comp (ref "D13")
      (value "RB521S-30")
      (footprint "easyedapro:SOD-523_L1.2-W0.8-LS1.6-RD")
      (fields (field (name "Manufacturer") "TWGMC(台湾迪嘉)"))
      (libsource (lib "easyedapro") (part "RB521S-30_C727120"))
    )
    (comp (ref "D14")
      (value "RB521S-30")
      (footprint "easyedapro:SOD-523_L1.2-W0.8-LS1.6-RD")
      (fields (field (name "Manufacturer") "TWGMC(台湾迪嘉)"))
      (libsource (lib "easyedapro") (part "RB521S-30_C727120"))
    )
    (comp (ref "D15")
      (value "RB521S-30")
      (footprint "easyedapro:SOD-523_L1.2-W0.8-LS1.6-RD")
      (fields (field (name "Manufacturer") "TWGMC(台湾迪嘉)"))
      (libsource (lib "easyedapro") (part "RB521S-30_C727120"))
    )
    (comp (ref "D16")
      (value "RB521S-30")
      (footprint "easyedapro:SOD-523_L1.2-W0.8-LS1.6-RD")
      (fields (field (name "Manufacturer") "TWGMC(台湾迪嘉)"))
      (libsource (lib "easyedapro") (part "RB521S-30_C727120"))
    )
    (comp (ref "D17")
      (value "RB521S-30")
      (footprint "easyedapro:SOD-523_L1.2-W0.8-LS1.6-RD")
      (fields (field (name "Manufacturer") "TWGMC(台湾迪嘉)"))
      (libsource (lib "easyedapro") (part "RB521S-30_C727120"))
    )
    (comp (ref "D18")
      (value "RB521S-30")
      (footprint "easyedapro:SOD-523_L1.2-W0.8-LS1.6-RD")
      (fields (field (name "Manufacturer") "TWGMC(台湾迪嘉)"))
      (libsource (lib "easyedapro") (part "RB521S-30_C727120"))
    )
    (comp (ref "D19")
      (value "RB521S-30")
      (footprint "easyedapro:SOD-523_L1.2-W0.8-LS1.6-RD")
      (fields (field (name "Manufacturer") "TWGMC(台湾迪嘉)"))
      (libsource (lib "easyedapro") (part "RB521S-30_C727120"))
    )
    (comp (ref "D20")
      (value "RB521S-30")
      (footprint "easyedapro:SOD-523_L1.2-W0.8-LS1.6-RD")
      (fields (field (name "Manufacturer") "TWGMC(台湾迪嘉)"))
      (libsource (lib "easyedapro") (part "RB521S-30_C727120"))
    )
    (comp (ref "D21")
      (value "RB521S-30")
      (footprint "easyedapro:SOD-523_L1.2-W0.8-LS1.6-RD")
      (fields (field (name "Manufacturer") "TWGMC(台湾迪嘉)"))
      (libsource (lib "easyedapro") (part "RB521S-30_C727120"))
    )
    (comp (ref "H3")
      (value "PZ254V-11-03P")
      (footprint "easyedapro:HDR-TH_3P-P2.54-V-M")
      (fields (field (name "Manufacturer") "XFCN(兴飞)"))
      (libsource (lib "easyedapro") (part "PZ254V-11-03P_C2937625"))
    )
    (comp (ref "J6")
      (value "B5B-XH-A-M(LF)(SN)")
      (footprint "easyedapro:CONN-TH_5P-P2.50_JST_B5B-XH-A-M")
      (fields (field (name "Manufacturer") "JST"))
      (libsource (lib "easyedapro") (part "B5B-XH-A-M(LF)(SN)"))
    )
    (comp (ref "J8")
      (value "B5B-XH-A-M(LF)(SN)")
      (footprint "easyedapro:CONN-TH_5P-P2.50_JST_B5B-XH-A-M")
      (fields (field (name "Manufacturer") "JST"))
      (libsource (lib "easyedapro") (part "B5B-XH-A-M(LF)(SN)"))
    )
    (comp (ref "J9")
      (value "ZX-XH2.54-3PZZ")
      (footprint "easyedapro:CONN-TH_3P-P2.54_2501S-3P")
      (fields (field (name "Manufacturer") "Megastar(兆星)"))
      (libsource (lib "easyedapro") (part "ZX-XH2.54-3PZZ"))
    )
    (comp (ref "J10")
      (value "B5B-XH-A-M(LF)(SN)")
      (footprint "easyedapro:CONN-TH_5P-P2.50_JST_B5B-XH-A-M")
      (fields (field (name "Manufacturer") "JST"))
      (libsource (lib "easyedapro") (part "B5B-XH-A-M(LF)(SN)"))
    )
    (comp (ref "J11")
      (value "ZX-XH2.54-3PZZ")
      (footprint "easyedapro:CONN-TH_3P-P2.54_2501S-3P")
      (fields (field (name "Manufacturer") "Megastar(兆星)"))
      (libsource (lib "easyedapro") (part "ZX-XH2.54-3PZZ"))
    )
    (comp (ref "J12")
      (value "B5B-XH-A-M(LF)(SN)")
      (footprint "easyedapro:CONN-TH_5P-P2.50_JST_B5B-XH-A-M")
      (fields (field (name "Manufacturer") "JST"))
      (libsource (lib "easyedapro") (part "B5B-XH-A-M(LF)(SN)"))
    )
    (comp (ref "J13")
      (value "ZX-XH2.54-3PZZ")
      (footprint "easyedapro:CONN-TH_3P-P2.54_2501S-3P")
      (fields (field (name "Manufacturer") "Megastar(兆星)"))
      (libsource (lib "easyedapro") (part "ZX-XH2.54-3PZZ"))
    )
    (comp (ref "J14")
      (value "ZX-XH2.54-3PZZ")
      (footprint "easyedapro:CONN-TH_3P-P2.54_2501S-3P")
      (fields (field (name "Manufacturer") "Megastar(兆星)"))
      (libsource (lib "easyedapro") (part "ZX-XH2.54-3PZZ"))
    )
    (comp (ref "J15")
      (value "B5B-XH-A-M(LF)(SN)")
      (footprint "easyedapro:CONN-TH_5P-P2.50_JST_B5B-XH-A-M")
      (fields (field (name "Manufacturer") "JST"))
      (libsource (lib "easyedapro") (part "B5B-XH-A-M(LF)(SN)"))
    )
    (comp (ref "J16")
      (value "ZX-XH2.54-3PZZ")
      (footprint "easyedapro:CONN-TH_3P-P2.54_2501S-3P")
      (fields (field (name "Manufacturer") "Megastar(兆星)"))
      (libsource (lib "easyedapro") (part "ZX-XH2.54-3PZZ"))
    )
    (comp (ref "J17")
      (value "B5B-XH-A-M(LF)(SN)")
      (footprint "easyedapro:CONN-TH_5P-P2.50_JST_B5B-XH-A-M")
      (fields (field (name "Manufacturer") "JST"))
      (libsource (lib "easyedapro") (part "B5B-XH-A-M(LF)(SN)"))
    )
    (comp (ref "J18")
      (value "ZX-XH2.54-3PZZ")
      (footprint "easyedapro:CONN-TH_3P-P2.54_2501S-3P")
      (fields (field (name "Manufacturer") "Megastar(兆星)"))
      (libsource (lib "easyedapro") (part "ZX-XH2.54-3PZZ"))
    )
    (comp (ref "J19")
      (value "ZX-XH2.54-3PZZ")
      (footprint "easyedapro:CONN-TH_3P-P2.54_2501S-3P")
      (fields (field (name "Manufacturer") "Megastar(兆星)"))
      (libsource (lib "easyedapro") (part "ZX-XH2.54-3PZZ"))
    )
    (comp (ref "J20")
      (value "ZX-XH2.54-3PZZ")
      (footprint "easyedapro:CONN-TH_3P-P2.54_2501S-3P")
      (fields (field (name "Manufacturer") "Megastar(兆星)"))
      (libsource (lib "easyedapro") (part "ZX-XH2.54-3PZZ"))
    )
    (comp (ref "J21")
      (value "ZX-XH2.54-3PZZ")
      (footprint "easyedapro:CONN-TH_3P-P2.54_2501S-3P")
      (fields (field (name "Manufacturer") "Megastar(兆星)"))
      (libsource (lib "easyedapro") (part "ZX-XH2.54-3PZZ"))
    )
    (comp (ref "J22")
      (value "ZX-XH2.54-3PZZ")
      (footprint "easyedapro:CONN-TH_3P-P2.54_2501S-3P")
      (fields (field (name "Manufacturer") "Megastar(兆星)"))
      (libsource (lib "easyedapro") (part "ZX-XH2.54-3PZZ"))
    )
    (comp (ref "J23")
      (value "B5B-XH-A-M(LF)(SN)")
      (footprint "easyedapro:CONN-TH_5P-P2.50_JST_B5B-XH-A-M")
      (fields (field (name "Manufacturer") "JST"))
      (libsource (lib "easyedapro") (part "B5B-XH-A-M(LF)(SN)"))
    )
    (comp (ref "J24")
      (value "B5B-XH-A-M(LF)(SN)")
      (footprint "easyedapro:CONN-TH_5P-P2.50_JST_B5B-XH-A-M")
      (fields (field (name "Manufacturer") "JST"))
      (libsource (lib "easyedapro") (part "B5B-XH-A-M(LF)(SN)"))
    )
    (comp (ref "LED8")
      (value "XL-1608UGC-04")
      (footprint "easyedapro:LED0603-RD_GREEN")
      (fields (field (name "Manufacturer") "XINGLIGHT(成兴光)"))
      (libsource (lib "easyedapro") (part "XL-1608UGC-04"))
    )
    (comp (ref "LED9")
      (value "XL-1608UGC-04")
      (footprint "easyedapro:LED0603-RD_GREEN")
      (fields (field (name "Manufacturer") "XINGLIGHT(成兴光)"))
      (libsource (lib "easyedapro") (part "XL-1608UGC-04"))
    )
    (comp (ref "LED10")
      (value "XL-1608UGC-04")
      (footprint "easyedapro:LED0603-RD_GREEN")
      (fields (field (name "Manufacturer") "XINGLIGHT(成兴光)"))
      (libsource (lib "easyedapro") (part "XL-1608UGC-04"))
    )
    (comp (ref "LED11")
      (value "XL-1608SURC-06")
      (footprint "easyedapro:LED0603-RD_RED")
      (fields (field (name "Manufacturer") "XINGLIGHT(成兴光)") (field (name "Contributor") "LCSC"))
      (libsource (lib "easyedapro") (part "XL-1608SURC-06"))
    )
    (comp (ref "LED12")
      (value "XL-1608UGC-04")
      (footprint "easyedapro:LED0603-RD_GREEN")
      (fields (field (name "Manufacturer") "XINGLIGHT(成兴光)"))
      (libsource (lib "easyedapro") (part "XL-1608UGC-04"))
    )
    (comp (ref "LED13")
      (value "XL-1608UGC-04")
      (footprint "easyedapro:LED0603-RD_GREEN")
      (fields (field (name "Manufacturer") "XINGLIGHT(成兴光)"))
      (libsource (lib "easyedapro") (part "XL-1608UGC-04"))
    )
    (comp (ref "LED14")
      (value "XL-1608UGC-04")
      (footprint "easyedapro:LED0603-RD_GREEN")
      (fields (field (name "Manufacturer") "XINGLIGHT(成兴光)"))
      (libsource (lib "easyedapro") (part "XL-1608UGC-04"))
    )
    (comp (ref "LED15")
      (value "XL-1608SURC-06")
      (footprint "easyedapro:LED0603-RD_RED")
      (fields (field (name "Manufacturer") "XINGLIGHT(成兴光)") (field (name "Contributor") "LCSC"))
      (libsource (lib "easyedapro") (part "XL-1608SURC-06"))
    )
    (comp (ref "LED16")
      (value "XL-1608UGC-04")
      (footprint "easyedapro:LED0603-RD_GREEN")
      (fields (field (name "Manufacturer") "XINGLIGHT(成兴光)"))
      (libsource (lib "easyedapro") (part "XL-1608UGC-04"))
    )
    (comp (ref "LED17")
      (value "XL-1608UGC-04")
      (footprint "easyedapro:LED0603-RD_GREEN")
      (fields (field (name "Manufacturer") "XINGLIGHT(成兴光)"))
      (libsource (lib "easyedapro") (part "XL-1608UGC-04"))
    )
    (comp (ref "LED18")
      (value "XL-1608UGC-04")
      (footprint "easyedapro:LED0603-RD_GREEN")
      (fields (field (name "Manufacturer") "XINGLIGHT(成兴光)"))
      (libsource (lib "easyedapro") (part "XL-1608UGC-04"))
    )
    (comp (ref "LED19")
      (value "XL-1608SURC-06")
      (footprint "easyedapro:LED0603-RD_RED")
      (fields (field (name "Manufacturer") "XINGLIGHT(成兴光)") (field (name "Contributor") "LCSC"))
      (libsource (lib "easyedapro") (part "XL-1608SURC-06"))
    )
    (comp (ref "LED20")
      (value "XL-1608SURC-06")
      (footprint "easyedapro:LED0603-RD_RED")
      (fields (field (name "Manufacturer") "XINGLIGHT(成兴光)") (field (name "Contributor") "LCSC"))
      (libsource (lib "easyedapro") (part "XL-1608SURC-06"))
    )
    (comp (ref "LED21")
      (value "XL-1608UGC-04")
      (footprint "easyedapro:LED0603-RD_GREEN")
      (fields (field (name "Manufacturer") "XINGLIGHT(成兴光)"))
      (libsource (lib "easyedapro") (part "XL-1608UGC-04"))
    )
    (comp (ref "LED22")
      (value "XL-1608UGC-04")
      (footprint "easyedapro:LED0603-RD_GREEN")
      (fields (field (name "Manufacturer") "XINGLIGHT(成兴光)"))
      (libsource (lib "easyedapro") (part "XL-1608UGC-04"))
    )
    (comp (ref "LED23")
      (value "XL-1608UGC-04")
      (footprint "easyedapro:LED0603-RD_GREEN")
      (fields (field (name "Manufacturer") "XINGLIGHT(成兴光)"))
      (libsource (lib "easyedapro") (part "XL-1608UGC-04"))
    )
    (comp (ref "LED24")
      (value "XL-1608SURC-06")
      (footprint "easyedapro:LED0603-RD_RED")
      (fields (field (name "Manufacturer") "XINGLIGHT(成兴光)") (field (name "Contributor") "LCSC"))
      (libsource (lib "easyedapro") (part "XL-1608SURC-06"))
    )
    (comp (ref "LED25")
      (value "XL-1608UGC-04")
      (footprint "easyedapro:LED0603-RD_GREEN")
      (fields (field (name "Manufacturer") "XINGLIGHT(成兴光)"))
      (libsource (lib "easyedapro") (part "XL-1608UGC-04"))
    )
    (comp (ref "LED26")
      (value "XL-1608UGC-04")
      (footprint "easyedapro:LED0603-RD_GREEN")
      (fields (field (name "Manufacturer") "XINGLIGHT(成兴光)"))
      (libsource (lib "easyedapro") (part "XL-1608UGC-04"))
    )
    (comp (ref "LED27")
      (value "XL-1608UGC-04")
      (footprint "easyedapro:LED0603-RD_GREEN")
      (fields (field (name "Manufacturer") "XINGLIGHT(成兴光)"))
      (libsource (lib "easyedapro") (part "XL-1608UGC-04"))
    )
    (comp (ref "LED28")
      (value "XL-1608SURC-06")
      (footprint "easyedapro:LED0603-RD_RED")
      (fields (field (name "Manufacturer") "XINGLIGHT(成兴光)") (field (name "Contributor") "LCSC"))
      (libsource (lib "easyedapro") (part "XL-1608SURC-06"))
    )
    (comp (ref "LED29")
      (value "XL-1608UGC-04")
      (footprint "easyedapro:LED0603-RD_GREEN")
      (fields (field (name "Manufacturer") "XINGLIGHT(成兴光)"))
      (libsource (lib "easyedapro") (part "XL-1608UGC-04"))
    )
    (comp (ref "LED30")
      (value "XL-1608UGC-04")
      (footprint "easyedapro:LED0603-RD_GREEN")
      (fields (field (name "Manufacturer") "XINGLIGHT(成兴光)"))
      (libsource (lib "easyedapro") (part "XL-1608UGC-04"))
    )
    (comp (ref "LED31")
      (value "XL-1608UGC-04")
      (footprint "easyedapro:LED0603-RD_GREEN")
      (fields (field (name "Manufacturer") "XINGLIGHT(成兴光)"))
      (libsource (lib "easyedapro") (part "XL-1608UGC-04"))
    )
    (comp (ref "LED32")
      (value "XL-1608SURC-06")
      (footprint "easyedapro:LED0603-RD_RED")
      (fields (field (name "Manufacturer") "XINGLIGHT(成兴光)") (field (name "Contributor") "LCSC"))
      (libsource (lib "easyedapro") (part "XL-1608SURC-06"))
    )
    (comp (ref "LED33")
      (value "XL-1608SURC-06")
      (footprint "easyedapro:LED0603-RD_RED")
      (fields (field (name "Manufacturer") "XINGLIGHT(成兴光)") (field (name "Contributor") "LCSC"))
      (libsource (lib "easyedapro") (part "XL-1608SURC-06"))
    )
    (comp (ref "LED34")
      (value "XL-1608SURC-06")
      (footprint "easyedapro:LED0603-RD_RED")
      (fields (field (name "Manufacturer") "XINGLIGHT(成兴光)") (field (name "Contributor") "LCSC"))
      (libsource (lib "easyedapro") (part "XL-1608SURC-06"))
    )
    (comp (ref "LED35")
      (value "XL-1608SURC-06")
      (footprint "easyedapro:LED0603-RD_RED")
      (fields (field (name "Manufacturer") "XINGLIGHT(成兴光)") (field (name "Contributor") "LCSC"))
      (libsource (lib "easyedapro") (part "XL-1608SURC-06"))
    )
    (comp (ref "LED36")
      (value "XL-1608UGC-04")
      (footprint "easyedapro:LED0603-RD_GREEN")
      (fields (field (name "Manufacturer") "XINGLIGHT(成兴光)"))
      (libsource (lib "easyedapro") (part "XL-1608UGC-04"))
    )
    (comp (ref "LED37")
      (value "XL-1608UGC-04")
      (footprint "easyedapro:LED0603-RD_GREEN")
      (fields (field (name "Manufacturer") "XINGLIGHT(成兴光)"))
      (libsource (lib "easyedapro") (part "XL-1608UGC-04"))
    )
    (comp (ref "LED38")
      (value "XL-1608UGC-04")
      (footprint "easyedapro:LED0603-RD_GREEN")
      (fields (field (name "Manufacturer") "XINGLIGHT(成兴光)"))
      (libsource (lib "easyedapro") (part "XL-1608UGC-04"))
    )
    (comp (ref "LED39")
      (value "XL-1608UGC-04")
      (footprint "easyedapro:LED0603-RD_GREEN")
      (fields (field (name "Manufacturer") "XINGLIGHT(成兴光)"))
      (libsource (lib "easyedapro") (part "XL-1608UGC-04"))
    )
    (comp (ref "LED40")
      (value "XL-1608UGC-04")
      (footprint "easyedapro:LED0603-RD_GREEN")
      (fields (field (name "Manufacturer") "XINGLIGHT(成兴光)"))
      (libsource (lib "easyedapro") (part "XL-1608UGC-04"))
    )
    (comp (ref "LED41")
      (value "XL-1608UGC-04")
      (footprint "easyedapro:LED0603-RD_GREEN")
      (fields (field (name "Manufacturer") "XINGLIGHT(成兴光)"))
      (libsource (lib "easyedapro") (part "XL-1608UGC-04"))
    )
    (comp (ref "OPT3")
      (value "TLP521GB-S")
      (footprint "easyedapro:OPTO-SMD-4_L6.5-W4.6-P2.54-LS10.0-TL")
      (fields (field (name "Manufacturer") "UMW(广东友台半导体)") (field (name "Contributor") "LCSC"))
      (libsource (lib "easyedapro") (part "TLP521GB-S"))
    )
    (comp (ref "OPT4")
      (value "TLP521GB-S")
      (footprint "easyedapro:OPTO-SMD-4_L6.5-W4.6-P2.54-LS10.0-TL")
      (fields (field (name "Manufacturer") "UMW(广东友台半导体)") (field (name "Contributor") "LCSC"))
      (libsource (lib "easyedapro") (part "TLP521GB-S"))
    )
    (comp (ref "OPT5")
      (value "TLP521GB-S")
      (footprint "easyedapro:OPTO-SMD-4_L6.5-W4.6-P2.54-LS10.0-TL")
      (fields (field (name "Manufacturer") "UMW(广东友台半导体)") (field (name "Contributor") "LCSC"))
      (libsource (lib "easyedapro") (part "TLP521GB-S"))
    )
    (comp (ref "OPT6")
      (value "TLP521GB-S")
      (footprint "easyedapro:OPTO-SMD-4_L6.5-W4.6-P2.54-LS10.0-TL")
      (fields (field (name "Manufacturer") "UMW(广东友台半导体)") (field (name "Contributor") "LCSC"))
      (libsource (lib "easyedapro") (part "TLP521GB-S"))
    )
    (comp (ref "OPT7")
      (value "TLP521GB-S")
      (footprint "easyedapro:OPTO-SMD-4_L6.5-W4.6-P2.54-LS10.0-TL")
      (fields (field (name "Manufacturer") "UMW(广东友台半导体)") (field (name "Contributor") "LCSC"))
      (libsource (lib "easyedapro") (part "TLP521GB-S"))
    )
    (comp (ref "OPT8")
      (value "TLP521GB-S")
      (footprint "easyedapro:OPTO-SMD-4_L6.5-W4.6-P2.54-LS10.0-TL")
      (fields (field (name "Manufacturer") "UMW(广东友台半导体)") (field (name "Contributor") "LCSC"))
      (libsource (lib "easyedapro") (part "TLP521GB-S"))
    )
    (comp (ref "OPT9")
      (value "TLP521GB-S")
      (footprint "easyedapro:OPTO-SMD-4_L6.5-W4.6-P2.54-LS10.0-TL")
      (fields (field (name "Manufacturer") "UMW(广东友台半导体)") (field (name "Contributor") "LCSC"))
      (libsource (lib "easyedapro") (part "TLP521GB-S"))
    )
    (comp (ref "OPT10")
      (value "TLP521GB-S")
      (footprint "easyedapro:OPTO-SMD-4_L6.5-W4.6-P2.54-LS10.0-TL")
      (fields (field (name "Manufacturer") "UMW(广东友台半导体)") (field (name "Contributor") "LCSC"))
      (libsource (lib "easyedapro") (part "TLP521GB-S"))
    )
    (comp (ref "OPT11")
      (value "TLP521GB-S")
      (footprint "easyedapro:OPTO-SMD-4_L6.5-W4.6-P2.54-LS10.0-TL")
      (fields (field (name "Manufacturer") "UMW(广东友台半导体)") (field (name "Contributor") "LCSC"))
      (libsource (lib "easyedapro") (part "TLP521GB-S"))
    )
    (comp (ref "OPT12")
      (value "TLP521GB-S")
      (footprint "easyedapro:OPTO-SMD-4_L6.5-W4.6-P2.54-LS10.0-TL")
      (fields (field (name "Manufacturer") "UMW(广东友台半导体)") (field (name "Contributor") "LCSC"))
      (libsource (lib "easyedapro") (part "TLP521GB-S"))
    )
    (comp (ref "PTC1")
      (value "12V 500mA")
      (footprint "easyedapro:F0805")
      (fields
        (field (name "Manufacturer Part") "SMD0805P050TF/12")
        (field (name "Manufacturer") "RUILON(瑞隆源)")
      )
      (libsource (lib "easyedapro") (part "SMD0805P050TF/12"))
    )
    (comp (ref "R36") (value "10kΩ") (libsource (lib "") (part "10kΩ_2")))
    (comp (ref "R37") (value "10kΩ") (libsource (lib "") (part "10kΩ_2")))
    (comp (ref "R38") (value "10kΩ") (libsource (lib "") (part "10kΩ_2")))
    (comp (ref "R41")
      (value "10kΩ")
      (fields
        (field (name "Manufacturer Part") "0402WGF1002TCE")
        (field (name "Manufacturer") "UNI-ROYAL(厚声)")
      )
      (libsource (lib "easyedapro") (part "RT0402BRD0710KL"))
    )
    (comp (ref "R42")
      (value "10kΩ")
      (fields
        (field (name "Manufacturer Part") "0402WGF1002TCE")
        (field (name "Manufacturer") "UNI-ROYAL(厚声)")
      )
      (libsource (lib "easyedapro") (part "RT0402BRD0710KL"))
    )
    (comp (ref "R43")
      (value "10kΩ")
      (fields
        (field (name "Manufacturer Part") "0402WGF1002TCE")
        (field (name "Manufacturer") "UNI-ROYAL(厚声)")
      )
      (libsource (lib "easyedapro") (part "RT0402BRD0710KL"))
    )
    (comp (ref "R44") (value "10kΩ") (libsource (lib "easyedapro") (part "10kΩ")))
    (comp (ref "R49") (value "10kΩ") (libsource (lib "easyedapro") (part "10kΩ")))
    (comp (ref "R50") (value "10kΩ") (libsource (lib "") (part "10kΩ_1")))
    (comp (ref "R51")
      (value "10kΩ")
      (fields
        (field (name "Manufacturer Part") "0402WGF1002TCE")
        (field (name "Manufacturer") "UNI-ROYAL(厚声)")
      )
      (libsource (lib "easyedapro") (part "RT0402BRD0710KL"))
    )
    (comp (ref "R52")
      (value "10kΩ")
      (fields
        (field (name "Manufacturer Part") "0402WGF1002TCE")
        (field (name "Manufacturer") "UNI-ROYAL(厚声)")
      )
      (libsource (lib "easyedapro") (part "RT0402BRD0710KL"))
    )
    (comp (ref "R53")
      (value "10kΩ")
      (fields
        (field (name "Manufacturer Part") "0402WGF1002TCE")
        (field (name "Manufacturer") "UNI-ROYAL(厚声)")
      )
      (libsource (lib "easyedapro") (part "RT0402BRD0710KL"))
    )
    (comp (ref "R56") (value "10kΩ") (libsource (lib "easyedapro") (part "10kΩ")))
    (comp (ref "R57") (value "10kΩ") (libsource (lib "") (part "10kΩ_1")))
    (comp (ref "R59")
      (value "10kΩ")
      (fields
        (field (name "Manufacturer Part") "0402WGF1002TCE")
        (field (name "Manufacturer") "UNI-ROYAL(厚声)")
      )
      (libsource (lib "easyedapro") (part "RT0402BRD0710KL"))
    )
    (comp (ref "R60")
      (value "10kΩ")
      (fields
        (field (name "Manufacturer Part") "0402WGF1002TCE")
        (field (name "Manufacturer") "UNI-ROYAL(厚声)")
      )
      (libsource (lib "easyedapro") (part "RT0402BRD0710KL"))
    )
    (comp (ref "R61")
      (value "10kΩ")
      (fields
        (field (name "Manufacturer Part") "0402WGF1002TCE")
        (field (name "Manufacturer") "UNI-ROYAL(厚声)")
      )
      (libsource (lib "easyedapro") (part "RT0402BRD0710KL"))
    )
    (comp (ref "R62") (value "10kΩ") (libsource (lib "easyedapro") (part "10kΩ")))
    (comp (ref "R63") (value "10kΩ") (libsource (lib "") (part "10kΩ_1")))
    (comp (ref "R65") (value "10kΩ") (libsource (lib "easyedapro") (part "10kΩ")))
    (comp (ref "R66")
      (value "10kΩ")
      (fields
        (field (name "Manufacturer Part") "0402WGF1002TCE")
        (field (name "Manufacturer") "UNI-ROYAL(厚声)")
      )
      (libsource (lib "easyedapro") (part "RT0402BRD0710KL"))
    )
    (comp (ref "R67")
      (value "10kΩ")
      (fields
        (field (name "Manufacturer Part") "0402WGF1002TCE")
        (field (name "Manufacturer") "UNI-ROYAL(厚声)")
      )
      (libsource (lib "easyedapro") (part "RT0402BRD0710KL"))
    )
    (comp (ref "R68")
      (value "10kΩ")
      (fields
        (field (name "Manufacturer Part") "0402WGF1002TCE")
        (field (name "Manufacturer") "UNI-ROYAL(厚声)")
      )
      (libsource (lib "easyedapro") (part "RT0402BRD0710KL"))
    )
    (comp (ref "R69") (value "10kΩ") (libsource (lib "") (part "10kΩ_1")))
    (comp (ref "R71") (value "10kΩ") (libsource (lib "") (part "10kΩ_2")))
    (comp (ref "R72") (value "10kΩ") (libsource (lib "easyedapro") (part "10kΩ")))
    (comp (ref "R73") (value "10kΩ") (libsource (lib "") (part "10kΩ_1")))
    (comp (ref "R75")
      (value "10kΩ")
      (fields
        (field (name "Manufacturer Part") "0402WGF1002TCE")
        (field (name "Manufacturer") "UNI-ROYAL(厚声)")
      )
      (libsource (lib "easyedapro") (part "RT0402BRD0710KL"))
    )
    (comp (ref "R76")
      (value "10kΩ")
      (fields
        (field (name "Manufacturer Part") "0402WGF1002TCE")
        (field (name "Manufacturer") "UNI-ROYAL(厚声)")
      )
      (libsource (lib "easyedapro") (part "RT0402BRD0710KL"))
    )
    (comp (ref "R77")
      (value "10kΩ")
      (fields
        (field (name "Manufacturer Part") "0402WGF1002TCE")
        (field (name "Manufacturer") "UNI-ROYAL(厚声)")
      )
      (libsource (lib "easyedapro") (part "RT0402BRD0710KL"))
    )
    (comp (ref "R78") (value "10kΩ") (libsource (lib "easyedapro") (part "10kΩ")))
    (comp (ref "R79") (value "10kΩ") (libsource (lib "") (part "10kΩ_1")))
    (comp (ref "R81") (value "10kΩ") (libsource (lib "easyedapro") (part "10kΩ")))
    (comp (ref "R82") (value "10kΩ") (libsource (lib "") (part "10kΩ_1")))
    (comp (ref "R84") (value "10kΩ") (libsource (lib "") (part "10kΩ_2")))
    (comp (ref "R85")
      (value "680Ω")
      (footprint "easyedapro:R0402")
      (fields (field (name "Manufacturer Part") "RMC04026801%N") (field (name "Manufacturer") "Tyohm(幸亚电阻)"))
      (libsource (lib "easyedapro") (part "RMC04026801%N"))
    )
    (comp (ref "R86")
      (value "680Ω")
      (footprint "easyedapro:R0402")
      (fields (field (name "Manufacturer Part") "RMC04026801%N") (field (name "Manufacturer") "Tyohm(幸亚电阻)"))
      (libsource (lib "easyedapro") (part "RMC04026801%N"))
    )
    (comp (ref "R87")
      (value "680Ω")
      (footprint "easyedapro:R0402")
      (fields (field (name "Manufacturer Part") "RMC04026801%N") (field (name "Manufacturer") "Tyohm(幸亚电阻)"))
      (libsource (lib "easyedapro") (part "RMC04026801%N"))
    )
    (comp (ref "R88")
      (value "680Ω")
      (footprint "easyedapro:R0402")
      (fields (field (name "Manufacturer Part") "RMC04026801%N") (field (name "Manufacturer") "Tyohm(幸亚电阻)"))
      (libsource (lib "easyedapro") (part "RMC04026801%N"))
    )
    (comp (ref "R89")
      (value "680Ω")
      (footprint "easyedapro:R0402")
      (fields (field (name "Manufacturer Part") "RMC04026801%N") (field (name "Manufacturer") "Tyohm(幸亚电阻)"))
      (libsource (lib "easyedapro") (part "RMC04026801%N"))
    )
    (comp (ref "R90")
      (value "680Ω")
      (footprint "easyedapro:R0402")
      (fields (field (name "Manufacturer Part") "RMC04026801%N") (field (name "Manufacturer") "Tyohm(幸亚电阻)"))
      (libsource (lib "easyedapro") (part "RMC04026801%N"))
    )
    (comp (ref "R91")
      (value "680Ω")
      (footprint "easyedapro:R0402")
      (fields (field (name "Manufacturer Part") "RMC04026801%N") (field (name "Manufacturer") "Tyohm(幸亚电阻)"))
      (libsource (lib "easyedapro") (part "RMC04026801%N"))
    )
    (comp (ref "R92")
      (value "680Ω")
      (footprint "easyedapro:R0402")
      (fields (field (name "Manufacturer Part") "RMC04026801%N") (field (name "Manufacturer") "Tyohm(幸亚电阻)"))
      (libsource (lib "easyedapro") (part "RMC04026801%N"))
    )
    (comp (ref "R93") (value "10kΩ") (libsource (lib "") (part "10kΩ_1")))
    (comp (ref "R94") (value "10kΩ") (libsource (lib "easyedapro") (part "10kΩ")))
    (comp (ref "R95") (value "10kΩ") (libsource (lib "") (part "10kΩ_1")))
    (comp (ref "R96") (value "10kΩ") (libsource (lib "easyedapro") (part "10kΩ")))
    (comp (ref "R97")
      (value "680Ω")
      (footprint "easyedapro:R0402")
      (fields (field (name "Manufacturer Part") "RMC04026801%N") (field (name "Manufacturer") "Tyohm(幸亚电阻)"))
      (libsource (lib "easyedapro") (part "RMC04026801%N"))
    )
    (comp (ref "R98")
      (value "680Ω")
      (footprint "easyedapro:R0402")
      (fields (field (name "Manufacturer Part") "RMC04026801%N") (field (name "Manufacturer") "Tyohm(幸亚电阻)"))
      (libsource (lib "easyedapro") (part "RMC04026801%N"))
    )
    (comp (ref "R99")
      (value "10kΩ")
      (fields
        (field (name "Manufacturer Part") "0402WGF1002TCE")
        (field (name "Manufacturer") "UNI-ROYAL(厚声)")
      )
      (libsource (lib "easyedapro") (part "RT0402BRD0710KL"))
    )
    (comp (ref "R100")
      (value "10kΩ")
      (fields
        (field (name "Manufacturer Part") "0402WGF1002TCE")
        (field (name "Manufacturer") "UNI-ROYAL(厚声)")
      )
      (libsource (lib "easyedapro") (part "RT0402BRD0710KL"))
    )
    (comp (ref "R101")
      (value "10kΩ")
      (fields
        (field (name "Manufacturer Part") "0402WGF1002TCE")
        (field (name "Manufacturer") "UNI-ROYAL(厚声)")
      )
      (libsource (lib "easyedapro") (part "RT0402BRD0710KL"))
    )
    (comp (ref "R102")
      (value "10kΩ")
      (fields
        (field (name "Manufacturer Part") "0402WGF1002TCE")
        (field (name "Manufacturer") "UNI-ROYAL(厚声)")
      )
      (libsource (lib "easyedapro") (part "RT0402BRD0710KL"))
    )
    (comp (ref "R103")
      (value "10kΩ")
      (fields
        (field (name "Manufacturer Part") "0402WGF1002TCE")
        (field (name "Manufacturer") "UNI-ROYAL(厚声)")
      )
      (libsource (lib "easyedapro") (part "RT0402BRD0710KL"))
    )
    (comp (ref "R104")
      (value "10kΩ")
      (fields
        (field (name "Manufacturer Part") "0402WGF1002TCE")
        (field (name "Manufacturer") "UNI-ROYAL(厚声)")
      )
      (libsource (lib "easyedapro") (part "RT0402BRD0710KL"))
    )
    (comp (ref "R107") (value "10kΩ") (libsource (lib "") (part "10kΩ_1")))
    (comp (ref "U9")
      (value "74AHCT595T16-13")
      (footprint "easyedapro:TSSOP-16_L5.0-W4.4-P0.65-LS6.4-BL")
      (fields (field (name "Manufacturer") "DIODES(美台)"))
      (libsource (lib "easyedapro") (part "74AHCT595T16-13"))
    )
    (comp (ref "U10")
      (value "74AHCT595T16-13")
      (footprint "easyedapro:TSSOP-16_L5.0-W4.4-P0.65-LS6.4-BL")
      (fields (field (name "Manufacturer") "DIODES(美台)"))
      (libsource (lib "easyedapro") (part "74AHCT595T16-13"))
    )
    (comp (ref "U11")
      (value "74AHCT595T16-13")
      (footprint "easyedapro:TSSOP-16_L5.0-W4.4-P0.65-LS6.4-BL")
      (fields (field (name "Manufacturer") "DIODES(美台)"))
      (libsource (lib "easyedapro") (part "74AHCT595T16-13"))
    )
  )
  (nets
    (net (code "1") (name "+3V3") (class "Default")
      (node (ref "C11") (pin "2") (pinfunction "2_2") (pintype "input"))
      (node (ref "C15") (pin "2") (pinfunction "2_2") (pintype "unspecified"))
      (node (ref "C16") (pin "1") (pinfunction "1_1") (pintype "unspecified"))
      (node (ref "C17") (pin "2") (pinfunction "2_2") (pintype "input"))
      (node (ref "C18") (pin "1") (pinfunction "1_1") (pintype "unspecified"))
      (node (ref "LED11") (pin "2") (pinfunction "A_2") (pintype "unspecified"))
      (node (ref "LED15") (pin "2") (pinfunction "A_2") (pintype "unspecified"))
      (node (ref "LED19") (pin "2") (pinfunction "A_2") (pintype "unspecified"))
      (node (ref "LED2") (pin "2") (pinfunction "A_2") (pintype "unspecified"))
      (node (ref "LED20") (pin "2") (pinfunction "A_2") (pintype "unspecified"))
      (node (ref "LED24") (pin "2") (pinfunction "A_2") (pintype "unspecified"))
      (node (ref "LED28") (pin "2") (pinfunction "A_2") (pintype "unspecified"))
      (node (ref "LED32") (pin "2") (pinfunction "A_2") (pintype "unspecified"))
      (node (ref "LED33") (pin "2") (pinfunction "A_2") (pintype "unspecified"))
      (node (ref "LED34") (pin "2") (pinfunction "A_2") (pintype "unspecified"))
      (node (ref "LED35") (pin "2") (pinfunction "A_2") (pintype "unspecified"))
      (node (ref "LED46") (pin "2") (pinfunction "A_2") (pintype "input"))
      (node (ref "R107") (pin "2") (pinfunction "2_2") (pintype "unspecified"))
      (node (ref "R30") (pin "2") (pinfunction "2_2") (pintype "unspecified"))
      (node (ref "R32") (pin "2") (pinfunction "2_2") (pintype "unspecified"))
      (node (ref "R50") (pin "2") (pinfunction "2_2") (pintype "unspecified"))
      (node (ref "R57") (pin "2") (pinfunction "2_2") (pintype "unspecified"))
      (node (ref "R63") (pin "2") (pinfunction "2_2") (pintype "unspecified"))
      (node (ref "R69") (pin "2") (pinfunction "2_2") (pintype "unspecified"))
      (node (ref "R73") (pin "2") (pinfunction "2_2") (pintype "unspecified"))
      (node (ref "R79") (pin "2") (pinfunction "2_2") (pintype "unspecified"))
      (node (ref "R82") (pin "2") (pinfunction "2_2") (pintype "unspecified"))
      (node (ref "R93") (pin "2") (pinfunction "2_2") (pintype "unspecified"))
      (node (ref "R95") (pin "2") (pinfunction "2_2") (pintype "unspecified"))
      (node (ref "SD1") (pin "4") (pinfunction "VDD_4") (pintype "input"))
      (node (ref "U14") (pin "2") (pinfunction "3V3_2") (pintype "unspecified"))
      (node (ref "U3") (pin "2") (pinfunction "Output_2") (pintype "unspecified"))
      (node (ref "U4") (pin "1") (pinfunction "VDD1_1") (pintype "unspecified"))
      (node (ref "U7") (pin "7") (pinfunction "REGIN_7") (pintype "unspecified"))
    )
    (net (code "2") (name "+5V") (class "Default")
      (node (ref "C10") (pin "1") (pinfunction "1_1") (pintype "unspecified"))
      (node (ref "C12") (pin "2") (pinfunction "2_2") (pintype "input"))
      (node (ref "C27") (pin "2") (pinfunction "2_2") (pintype "unspecified"))
      (node (ref "C28") (pin "2") (pinfunction "2_2") (pintype "unspecified"))
      (node (ref "C29") (pin "2") (pinfunction "2_2") (pintype "unspecified"))
      (node (ref "C31") (pin "1") (pinfunction "1_1") (pintype "unspecified"))
      (node (ref "C32") (pin "1") (pinfunction "1_1") (pintype "unspecified"))
      (node (ref "C4") (pin "2") (pinfunction "2_2") (pintype "input"))
      (node (ref "C5") (pin "1") (pinfunction "1_1") (pintype "input"))
      (node (ref "D25") (pin "2") (pinfunction "A_2") (pintype "unspecified"))
      (node (ref "H3") (pin "1") (pinfunction "1_1") (pintype "unspecified"))
      (node (ref "J10") (pin "1") (pinfunction "1_1") (pintype "unspecified"))
      (node (ref "J12") (pin "1") (pinfunction "1_1") (pintype "unspecified"))
      (node (ref "J15") (pin "1") (pinfunction "1_1") (pintype "unspecified"))
      (node (ref "J17") (pin "1") (pinfunction "1_1") (pintype "unspecified"))
      (node (ref "J23") (pin "1") (pinfunction "1_1") (pintype "unspecified"))
      (node (ref "J24") (pin "1") (pinfunction "1_1") (pintype "unspecified"))
      (node (ref "J6") (pin "1") (pinfunction "1_1") (pintype "unspecified"))
      (node (ref "J67") (pin "3") (pinfunction "3_3") (pintype "unspecified"))
      (node (ref "J8") (pin "1") (pinfunction "1_1") (pintype "unspecified"))
      (node (ref "L1") (pin "2") (pinfunction "2_2") (pintype "unspecified"))
      (node (ref "LED47") (pin "2") (pinfunction "A_2") (pintype "input"))
      (node (ref "PS1") (pin "2") (pinfunction "+VIN_2") (pintype "unspecified"))
      (node (ref "R121") (pin "2") (pinfunction "2_2") (pintype "input"))
      (node (ref "R84") (pin "2") (pinfunction "2_2") (pintype "input"))
      (node (ref "RJ1") (pin "3") (pinfunction "3_3") (pintype "unspecified"))
      (node (ref "U10") (pin "16") (pinfunction "VCC_16") (pintype "unspecified"))
      (node (ref "U11") (pin "16") (pinfunction "VCC_16") (pintype "unspecified"))
      (node (ref "U2") (pin "14") (pinfunction "VCC_14") (pintype "unspecified"))
      (node (ref "U3") (pin "3") (pinfunction "Input_3") (pintype "unspecified"))
      (node (ref "U9") (pin "16") (pinfunction "VCC_16") (pintype "unspecified"))
    )
    (net (code "3") (name "+5V_ISO") (class "Default")
      (node (ref "C13") (pin "1") (pinfunction "1_1") (pintype "unspecified"))
      (node (ref "C14") (pin "2") (pinfunction "2_2") (pintype "unspecified"))
      (node (ref "C9") (pin "2") (pinfunction "2_2") (pintype "input"))
      (node (ref "PS1") (pin "5") (pinfunction "+VO_5") (pintype "unspecified"))
      (node (ref "R10") (pin "2") (pinfunction "2_2") (pintype "input"))
      (node (ref "R13") (pin "2") (pinfunction "2_2") (pintype "input"))
      (node (ref "R15") (pin "2") (pinfunction "2_2") (pintype "input"))
      (node (ref "U4") (pin "8") (pinfunction "VDD2_8") (pintype "unspecified"))
      (node (ref "U5") (pin "8") (pinfunction "VCC_8") (pintype "unspecified"))
    )
    (net (code "4") (name "+12V") (class "Default")
      (node (ref "C2") (pin "2") (pinfunction "2_2") (pintype "unspecified"))
      (node (ref "C26") (pin "2") (pinfunction "2_2") (pintype "unspecified"))
      (node (ref "C3") (pin "2") (pinfunction "2_2") (pintype "unspecified"))
      (node (ref "D2") (pin "1") (pinfunction "K_1") (pintype "input"))
      (node (ref "D3") (pin "1") (pinfunction "K_1") (pintype "unspecified"))
      (node (ref "D4") (pin "1") (pinfunction "K_1") (pintype "unspecified"))
      (node (ref "H3") (pin "3") (pinfunction "3_3") (pintype "unspecified"))
      (node (ref "J67") (pin "2") (pinfunction "2_2") (pintype "unspecified"))
      (node (ref "Q1") (pin "3") (pinfunction "S_3") (pintype "unspecified"))
      (node (ref "RJ1") (pin "2") (pinfunction "2_2") (pintype "unspecified"))
      (node (ref "TB1") (pin "3") (pinfunction "3_3") (pintype "unspecified"))
      (node (ref "TB1") (pin "5") (pinfunction "5_5") (pintype "unspecified"))
      (node (ref "U1") (pin "2") (pinfunction "VIN_2") (pintype "unspecified"))
      (node (ref "U8") (pin "8") (pinfunction "VCC+_8") (pintype "unspecified"))
    )
    (net (code "5") (name "A_DIR") (class "Default")
      (node (ref "J12") (pin "3") (pinfunction "3_3") (pintype "unspecified"))
      (node (ref "R61") (pin "2") (pinfunction "2_2") (pintype "unspecified"))
      (node (ref "U10") (pin "2") (pinfunction "Q2_2") (pintype "unspecified"))
    )
    (net (code "6") (name "A_ENABLE") (class "Default")
      (node (ref "J12") (pin "5") (pinfunction "5_5") (pintype "unspecified"))
      (node (ref "R59") (pin "2") (pinfunction "2_2") (pintype "unspecified"))
      (node (ref "U10") (pin "3") (pinfunction "Q3_3") (pintype "unspecified"))
    )
    (net (code "7") (name "A_STEP") (class "Default")
      (node (ref "J12") (pin "4") (pinfunction "4_4") (pintype "unspecified"))
      (node (ref "R60") (pin "2") (pinfunction "2_2") (pintype "unspecified"))
      (node (ref "U10") (pin "1") (pinfunction "Q1_1") (pintype "unspecified"))
    )
    (net (code "8") (name "B_DIR") (class "Default")
      (node (ref "J15") (pin "3") (pinfunction "3_3") (pintype "unspecified"))
      (node (ref "R68") (pin "2") (pinfunction "2_2") (pintype "unspecified"))
      (node (ref "U10") (pin "5") (pinfunction "Q5_5") (pintype "unspecified"))
    )
    (net (code "9") (name "B_ENABLE") (class "Default")
      (node (ref "J15") (pin "5") (pinfunction "5_5") (pintype "unspecified"))
      (node (ref "R66") (pin "2") (pinfunction "2_2") (pintype "unspecified"))
      (node (ref "U10") (pin "6") (pinfunction "Q6_6") (pintype "unspecified"))
    )
    (net (code "10") (name "B_STEP") (class "Default")
      (node (ref "J15") (pin "4") (pinfunction "4_4") (pintype "unspecified"))
      (node (ref "R67") (pin "2") (pinfunction "2_2") (pintype "unspecified"))
      (node (ref "U10") (pin "4") (pinfunction "Q4_4") (pintype "unspecified"))
    )
    (net (code "11") (name "CS_SD") (class "Default")
      (node (ref "SD1") (pin "2") (pinfunction "CDDAT3(CS)_2") (pintype "bidirectional"))
      (node (ref "U14") (pin "17") (pinfunction "IO9_17") (pintype "unspecified"))
    )
    (net (code "12") (name "C_DIR") (class "Default")
      (node (ref "J17") (pin "3") (pinfunction "3_3") (pintype "unspecified"))
      (node (ref "R77") (pin "2") (pinfunction "2_2") (pintype "unspecified"))
      (node (ref "U11") (pin "15") (pinfunction "Q0_15") (pintype "unspecified"))
    )
    (net (code "13") (name "C_ENABLE") (class "Default")
      (node (ref "J17") (pin "5") (pinfunction "5_5") (pintype "unspecified"))
      (node (ref "R75") (pin "2") (pinfunction "2_2") (pintype "unspecified"))
      (node (ref "U11") (pin "1") (pinfunction "Q1_1") (pintype "unspecified"))
    )
    (net (code "14") (name "C_STEP") (class "Default")
      (node (ref "J17") (pin "4") (pinfunction "4_4") (pintype "unspecified"))
      (node (ref "R76") (pin "2") (pinfunction "2_2") (pintype "unspecified"))
      (node (ref "U10") (pin "7") (pinfunction "Q7_7") (pintype "unspecified"))
    )
    (net (code "15") (name "DTR") (class "Default")
      (node (ref "Q6") (pin "2") (pinfunction "E_2") (pintype "unspecified"))
      (node (ref "R28") (pin "1") (pinfunction "1_1") (pintype "input"))
      (node (ref "U7") (pin "28") (pinfunction "DTR_28") (pintype "unspecified"))
    )
    (net (code "16") (name "ESP32_EN") (class "Default")
      (node (ref "C19") (pin "2") (pinfunction "2_2") (pintype "unspecified"))
      (node (ref "Q5") (pin "3") (pinfunction "C_3") (pintype "unspecified"))
      (node (ref "R30") (pin "1") (pinfunction "1_1") (pintype "unspecified"))
      (node (ref "SW1") (pin "2") (pinfunction "2_2") (pintype "unspecified"))
      (node (ref "U14") (pin "3") (pinfunction "EN_3") (pintype "unspecified"))
    )
    (net (code "17") (name "EXP_RXD") (class "Default")
      (node (ref "R26") (pin "1") (pinfunction "1_1") (pintype "input"))
      (node (ref "U14") (pin "28") (pinfunction "IO35_28") (pintype "unspecified"))
    )
    (net (code "18") (name "GND") (class "Default")
      (node (ref "C10") (pin "2") (pinfunction "2_2") (pintype "unspecified"))
      (node (ref "C11") (pin "1") (pinfunction "1_1") (pintype "input"))
      (node (ref "C12") (pin "1") (pinfunction "1_1") (pintype "input"))
      (node (ref "C15") (pin "1") (pinfunction "1_1") (pintype "unspecified"))
      (node (ref "C16") (pin "2") (pinfunction "2_2") (pintype "unspecified"))
      (node (ref "C17") (pin "1") (pinfunction "1_1") (pintype "input"))
      (node (ref "C18") (pin "2") (pinfunction "2_2") (pintype "unspecified"))
      (node (ref "C19") (pin "1") (pinfunction "1_1") (pintype "unspecified"))
      (node (ref "C2") (pin "1") (pinfunction "1_1") (pintype "unspecified"))
      (node (ref "C21") (pin "1") (pinfunction "1_1") (pintype "input"))
      (node (ref "C22") (pin "2") (pinfunction "2_2") (pintype "unspecified"))
      (node (ref "C23") (pin "1") (pinfunction "1_1") (pintype "input"))
      (node (ref "C24") (pin "2") (pinfunction "2_2") (pintype "unspecified"))
      (node (ref "C25") (pin "1") (pinfunction "1_1") (pintype "unspecified"))
      (node (ref "C26") (pin "1") (pinfunction "1_1") (pintype "unspecified"))
      (node (ref "C27") (pin "1") (pinfunction "1_1") (pintype "unspecified"))
      (node (ref "C28") (pin "1") (pinfunction "1_1") (pintype "unspecified"))
      (node (ref "C29") (pin "1") (pinfunction "1_1") (pintype "unspecified"))
      (node (ref "C3") (pin "1") (pinfunction "1_1") (pintype "unspecified"))
      (node (ref "C30") (pin "1") (pinfunction "1_1") (pintype "unspecified"))
      (node (ref "C31") (pin "2") (pinfunction "2_2") (pintype "unspecified"))
      (node (ref "C32") (pin "2") (pinfunction "2_2") (pintype "unspecified"))
      (node (ref "C4") (pin "1") (pinfunction "1_1") (pintype "input"))
      (node (ref "C5") (pin "2") (pinfunction "2_2") (pintype "input"))
      (node (ref "C6") (pin "1") (pinfunction "1_1") (pintype "input"))
      (node (ref "C7") (pin "1") (pinfunction "1_1") (pintype "input"))
      (node (ref "D1") (pin "2") (pinfunction "A_2") (pintype "unspecified"))
      (node (ref "D10") (pin "1") (pinfunction "1_1") (pintype "unspecified"))
      (node (ref "D11") (pin "1") (pinfunction "1_1") (pintype "unspecified"))
      (node (ref "D22") (pin "1") (pinfunction "1_1") (pintype "unspecified"))
      (node (ref "D23") (pin "1") (pinfunction "1_1") (pintype "unspecified"))
      (node (ref "D24") (pin "1") (pinfunction "1_1") (pintype "unspecified"))
      (node (ref "D6") (pin "1") (pinfunction "1_1") (pintype "unspecified"))
      (node (ref "D7") (pin "1") (pinfunction "1_1") (pintype "unspecified"))
      (node (ref "D9") (pin "1") (pinfunction "1_1") (pintype "unspecified"))
      (node (ref "J1") (pin "2") (pinfunction "2_2") (pintype "unspecified"))
      (node (ref "J10") (pin "2") (pinfunction "2_2") (pintype "unspecified"))
      (node (ref "J11") (pin "2") (pinfunction "2_2") (pintype "unspecified"))
      (node (ref "J12") (pin "2") (pinfunction "2_2") (pintype "unspecified"))
      (node (ref "J13") (pin "2") (pinfunction "2_2") (pintype "unspecified"))
      (node (ref "J14") (pin "2") (pinfunction "2_2") (pintype "unspecified"))
      (node (ref "J15") (pin "2") (pinfunction "2_2") (pintype "unspecified"))
      (node (ref "J16") (pin "2") (pinfunction "2_2") (pintype "unspecified"))
      (node (ref "J17") (pin "2") (pinfunction "2_2") (pintype "unspecified"))
      (node (ref "J18") (pin "2") (pinfunction "2_2") (pintype "unspecified"))
      (node (ref "J19") (pin "2") (pinfunction "2_2") (pintype "unspecified"))
      (node (ref "J2") (pin "2") (pinfunction "2_2") (pintype "unspecified"))
      (node (ref "J20") (pin "2") (pinfunction "2_2") (pintype "unspecified"))
      (node (ref "J21") (pin "2") (pinfunction "2_2") (pintype "unspecified"))
      (node (ref "J22") (pin "2") (pinfunction "2_2") (pintype "unspecified"))
      (node (ref "J23") (pin "2") (pinfunction "2_2") (pintype "unspecified"))
      (node (ref "J24") (pin "2") (pinfunction "2_2") (pintype "unspecified"))
      (node (ref "J3") (pin "2") (pinfunction "2_2") (pintype "unspecified"))
      (node (ref "J4") (pin "2") (pinfunction "2_2") (pintype "unspecified"))
      (node (ref "J6") (pin "2") (pinfunction "2_2") (pintype "unspecified"))
      (node (ref "J67") (pin "1") (pinfunction "1_1") (pintype "unspecified"))
      (node (ref "J67") (pin "12") (pinfunction "12_12") (pintype "unspecified"))
      (node (ref "J7") (pin "5") (pinfunction "5_5") (pintype "unspecified"))
      (node (ref "J8") (pin "2") (pinfunction "2_2") (pintype "unspecified"))
      (node (ref "J9") (pin "2") (pinfunction "2_2") (pintype "unspecified"))
      (node (ref "LED10") (pin "1") (pinfunction "K_1") (pintype "input"))
      (node (ref "LED12") (pin "1") (pinfunction "K_1") (pintype "input"))
      (node (ref "LED13") (pin "1") (pinfunction "K_1") (pintype "input"))
      (node (ref "LED14") (pin "1") (pinfunction "K_1") (pintype "input"))
      (node (ref "LED16") (pin "1") (pinfunction "K_1") (pintype "input"))
      (node (ref "LED17") (pin "1") (pinfunction "K_1") (pintype "input"))
      (node (ref "LED18") (pin "1") (pinfunction "K_1") (pintype "input"))
      (node (ref "LED21") (pin "1") (pinfunction "K_1") (pintype "input"))
      (node (ref "LED22") (pin "1") (pinfunction "K_1") (pintype "input"))
      (node (ref "LED23") (pin "1") (pinfunction "K_1") (pintype "input"))
      (node (ref "LED25") (pin "1") (pinfunction "K_1") (pintype "input"))
      (node (ref "LED26") (pin "1") (pinfunction "K_1") (pintype "input"))
      (node (ref "LED27") (pin "1") (pinfunction "K_1") (pintype "input"))
      (node (ref "LED29") (pin "1") (pinfunction "K_1") (pintype "input"))
      (node (ref "LED30") (pin "1") (pinfunction "K_1") (pintype "input"))
      (node (ref "LED31") (pin "1") (pinfunction "K_1") (pintype "input"))
      (node (ref "LED36") (pin "1") (pinfunction "K_1") (pintype "input"))
      (node (ref "LED37") (pin "1") (pinfunction "K_1") (pintype "input"))
      (node (ref "LED38") (pin "1") (pinfunction "K_1") (pintype "input"))
      (node (ref "LED39") (pin "1") (pinfunction "K_1") (pintype "input"))
      (node (ref "LED40") (pin "1") (pinfunction "K_1") (pintype "input"))
      (node (ref "LED41") (pin "1") (pinfunction "K_1") (pintype "input"))
      (node (ref "LED8") (pin "1") (pinfunction "K_1") (pintype "input"))
      (node (ref "LED9") (pin "1") (pinfunction "K_1") (pintype "input"))
      (node (ref "MH1") (pin "1") (pinfunction "1_1") (pintype "unspecified"))
      (node (ref "MH2") (pin "1") (pinfunction "1_1") (pintype "unspecified"))
      (node (ref "MH3") (pin "1") (pinfunction "1_1") (pintype "unspecified"))
      (node (ref "MH4") (pin "1") (pinfunction "1_1") (pintype "unspecified"))
      (node (ref "OPT1") (pin "2") (pinfunction "2_2") (pintype "unspecified"))
      (node (ref "OPT10") (pin "3") (pinfunction "3_3") (pintype "unspecified"))
      (node (ref "OPT11") (pin "3") (pinfunction "3_3") (pintype "unspecified"))
      (node (ref "OPT12") (pin "3") (pinfunction "3_3") (pintype "unspecified"))
      (node (ref "OPT2") (pin "2") (pinfunction "2_2") (pintype "unspecified"))
      (node (ref "OPT3") (pin "3") (pinfunction "3_3") (pintype "unspecified"))
      (node (ref "OPT4") (pin "3") (pinfunction "3_3") (pintype "unspecified"))
      (node (ref "OPT5") (pin "3") (pinfunction "3_3") (pintype "unspecified"))
      (node (ref "OPT6") (pin "3") (pinfunction "3_3") (pintype "unspecified"))
      (node (ref "OPT7") (pin "3") (pinfunction "3_3") (pintype "unspecified"))
      (node (ref "OPT8") (pin "3") (pinfunction "3_3") (pintype "unspecified"))
      (node (ref "OPT9") (pin "3") (pinfunction "3_3") (pintype "unspecified"))
      (node (ref "PS1") (pin "1") (pinfunction "-VIN_1") (pintype "unspecified"))
      (node (ref "Q2") (pin "3") (pinfunction "S_3") (pintype "unspecified"))
      (node (ref "Q3") (pin "3") (pinfunction "S_3") (pintype "unspecified"))
      (node (ref "R1") (pin "1") (pinfunction "1_1") (pintype "unspecified"))
      (node (ref "R105") (pin "1") (pinfunction "1_1") (pintype "input"))
      (node (ref "R106") (pin "1") (pinfunction "1_1") (pintype "input"))
      (node (ref "R110") (pin "2") (pinfunction "2_2") (pintype "unspecified"))
      (node (ref "R111") (pin "2") (pinfunction "2_2") (pintype "unspecified"))
      (node (ref "R112") (pin "2") (pinfunction "2_2") (pintype "unspecified"))
      (node (ref "R113") (pin "2") (pinfunction "2_2") (pintype "unspecified"))
      (node (ref "R116") (pin "1") (pinfunction "1_1") (pintype "unspecified"))
      (node (ref "R117") (pin "1") (pinfunction "1_1") (pintype "unspecified"))
      (node (ref "R118") (pin "1") (pinfunction "1_1") (pintype "unspecified"))
      (node (ref "R119") (pin "1") (pinfunction "1_1") (pintype "unspecified"))
      (node (ref "R12") (pin "1") (pinfunction "1_1") (pintype "unspecified"))
      (node (ref "R120") (pin "1") (pinfunction "1_1") (pintype "unspecified"))
      (node (ref "R3") (pin "1") (pinfunction "1_1") (pintype "input"))
      (node (ref "R31") (pin "1") (pinfunction "1_1") (pintype "input"))
      (node (ref "R33") (pin "1") (pinfunction "1_1") (pintype "input"))
      (node (ref "R34") (pin "1") (pinfunction "1_1") (pintype "input"))
      (node (ref "R35") (pin "1") (pinfunction "1_1") (pintype "input"))
      (node (ref "R54") (pin "1") (pinfunction "1_1") (pintype "input"))
      (node (ref "R71") (pin "1") (pinfunction "1_1") (pintype "input"))
      (node (ref "RJ1") (pin "1") (pinfunction "1_1") (pintype "unspecified"))
      (node (ref "RJ1") (pin "6") (pinfunction "6_6") (pintype "unspecified"))
      (node (ref "SD1") (pin "10") (pinfunction "GND_10") (pintype "input"))
      (node (ref "SD1") (pin "11") (pinfunction "GND_11") (pintype "input"))
      (node (ref "SD1") (pin "12") (pinfunction "GND_12") (pintype "input"))
      (node (ref "SD1") (pin "13") (pinfunction "GND_13") (pintype "input"))
      (node (ref "SD1") (pin "6") (pinfunction "VSS_6") (pintype "input"))
      (node (ref "TB1") (pin "2") (pinfunction "2_2") (pintype "unspecified"))
      (node (ref "U1") (pin "7") (pinfunction "GND_7") (pintype "unspecified"))
      (node (ref "U1") (pin "9") (pinfunction "EP_9") (pintype "unspecified"))
      (node (ref "U10") (pin "13") (pinfunction "OE#_13") (pintype "unspecified"))
      (node (ref "U10") (pin "8") (pinfunction "GND_8") (pintype "unspecified"))
      (node (ref "U11") (pin "13") (pinfunction "OE#_13") (pintype "unspecified"))
      (node (ref "U11") (pin "8") (pinfunction "GND_8") (pintype "unspecified"))
      (node (ref "U13") (pin "2") (pinfunction "GND_2") (pintype "unspecified"))
      (node (ref "U14") (pin "1") (pinfunction "GND_1") (pintype "unspecified"))
      (node (ref "U14") (pin "40") (pinfunction "GND_40") (pintype "unspecified"))
      (node (ref "U14") (pin "41") (pinfunction "GND_41") (pintype "unspecified"))
      (node (ref "U2") (pin "1") (pinfunction "1OE#_1") (pintype "unspecified"))
      (node (ref "U2") (pin "10") (pinfunction "3OE#_10") (pintype "unspecified"))
      (node (ref "U2") (pin "13") (pinfunction "4OE#_13") (pintype "unspecified"))
      (node (ref "U2") (pin "4") (pinfunction "2OE#_4") (pintype "unspecified"))
      (node (ref "U2") (pin "7") (pinfunction "GND_7") (pintype "unspecified"))
      (node (ref "U3") (pin "1") (pinfunction "GND/ADJ_1") (pintype "unspecified"))
      (node (ref "U4") (pin "4") (pinfunction "GND1_4") (pintype "unspecified"))
      (node (ref "U7") (pin "29") (pinfunction "EP_29") (pintype "unspecified"))
      (node (ref "U7") (pin "3") (pinfunction "GND_3") (pintype "unspecified"))
      (node (ref "U8") (pin "4") (pinfunction "VCC-_4") (pintype "unspecified"))
      (node (ref "U8") (pin "5") (pinfunction "IN2+_5") (pintype "unspecified"))
      (node (ref "U9") (pin "13") (pinfunction "OE#_13") (pintype "unspecified"))
      (node (ref "U9") (pin "8") (pinfunction "GND_8") (pintype "unspecified"))
      (node (ref "USB1") (pin "1") (pinfunction "GND_1") (pintype "unspecified"))
      (node (ref "USB1") (pin "12") (pinfunction "GND_12") (pintype "unspecified"))
      (node (ref "USB1") (pin "13") (pinfunction "SHELL_13") (pintype "unspecified"))
      (node (ref "USB1") (pin "14") (pinfunction "SHELL_14") (pintype "unspecified"))
      (node (ref "USB2") (pin "1") (pinfunction "GND_1") (pintype "unspecified"))
      (node (ref "USB2") (pin "12") (pinfunction "GND_12") (pintype "unspecified"))
      (node (ref "USB2") (pin "13") (pinfunction "SHELL_13") (pintype "unspecified"))
      (node (ref "USB2") (pin "14") (pinfunction "SHELL_14") (pintype "unspecified"))
    )
    (net (code "19") (name "GND_ISO") (class "Default")
      (node (ref "C13") (pin "2") (pinfunction "2_2") (pintype "unspecified"))
      (node (ref "C14") (pin "1") (pinfunction "1_1") (pintype "unspecified"))
      (node (ref "C9") (pin "1") (pinfunction "1_1") (pintype "input"))
      (node (ref "D5") (pin "3") (pinfunction "3_3") (pintype "unspecified"))
      (node (ref "J5") (pin "3") (pinfunction "3_3") (pintype "unspecified"))
      (node (ref "PS1") (pin "4") (pinfunction "0V_4") (pintype "unspecified"))
      (node (ref "Q4") (pin "2") (pinfunction "S_2") (pintype "unspecified"))
      (node (ref "R10") (pin "1") (pinfunction "1_1") (pintype "input"))
      (node (ref "R20") (pin "1") (pinfunction "1_1") (pintype "input"))
      (node (ref "U4") (pin "5") (pinfunction "GND2_5") (pintype "unspecified"))
      (node (ref "U5") (pin "5") (pinfunction "GND_5") (pintype "unspecified"))
    )
    (net (code "20") (name "GPIO_0") (class "Default")
      (node (ref "Q6") (pin "3") (pinfunction "C_3") (pintype "unspecified"))
      (node (ref "R27") (pin "1") (pinfunction "1_1") (pintype "input"))
      (node (ref "R32") (pin "1") (pinfunction "1_1") (pintype "unspecified"))
      (node (ref "SW2") (pin "2") (pinfunction "2_2") (pintype "unspecified"))
      (node (ref "U14") (pin "27") (pinfunction "IO0_27") (pintype "unspecified"))
    )
    (net (code "21") (name "GPIO_3") (class "Default")
      (node (ref "OPT12") (pin "4") (pinfunction "4_4") (pintype "unspecified"))
      (node (ref "R95") (pin "1") (pinfunction "1_1") (pintype "unspecified"))
      (node (ref "R96") (pin "1") (pinfunction "1_1") (pintype "unspecified"))
      (node (ref "U14") (pin "15") (pinfunction "IO3_15") (pintype "unspecified"))
    )
    (net (code "22") (name "GPIO_4") (class "Default")
      (node (ref "R11") (pin "1") (pinfunction "1_1") (pintype "input"))
      (node (ref "R119") (pin "2") (pinfunction "2_2") (pintype "unspecified"))
      (node (ref "R5") (pin "1") (pinfunction "1_1") (pintype "input"))
      (node (ref "U14") (pin "4") (pinfunction "IO4_4") (pintype "unspecified"))
    )
    (net (code "23") (name "GPIO_5") (class "Default")
      (node (ref "R118") (pin "2") (pinfunction "2_2") (pintype "unspecified"))
      (node (ref "R16") (pin "1") (pinfunction "1_1") (pintype "input"))
      (node (ref "R8") (pin "1") (pinfunction "1_1") (pintype "input"))
      (node (ref "U14") (pin "5") (pinfunction "IO5_5") (pintype "unspecified"))
    )
    (net (code "24") (name "GPIO_6") (class "Default")
      (node (ref "R48") (pin "1") (pinfunction "1_1") (pintype "input"))
      (node (ref "U14") (pin "6") (pinfunction "IO6_6") (pintype "unspecified"))
    )
    (net (code "25") (name "GPIO_7") (class "Default")
      (node (ref "R39") (pin "1") (pinfunction "1_1") (pintype "input"))
      (node (ref "U14") (pin "7") (pinfunction "IO7_7") (pintype "unspecified"))
    )
    (net (code "26") (name "GPIO_8") (class "Default")
      (node (ref "R40") (pin "1") (pinfunction "1_1") (pintype "input"))
      (node (ref "U14") (pin "12") (pinfunction "IO8_12") (pintype "unspecified"))
    )
    (net (code "27") (name "GPIO_10") (class "Default")
      (node (ref "J67") (pin "6") (pinfunction "6_6") (pintype "unspecified"))
      (node (ref "U14") (pin "18") (pinfunction "IO10_18") (pintype "unspecified"))
    )
    (net (code "28") (name "GPIO_13") (class "Default")
      (node (ref "J67") (pin "5") (pinfunction "5_5") (pintype "unspecified"))
      (node (ref "U14") (pin "21") (pinfunction "IO13_21") (pintype "unspecified"))
    )
    (net (code "29") (name "GPIO_14") (class "Default")
      (node (ref "J67") (pin "4") (pinfunction "4_4") (pintype "unspecified"))
      (node (ref "U14") (pin "22") (pinfunction "IO14_22") (pintype "unspecified"))
    )
    (net (code "30") (name "GPIO_15") (class "Default")
      (node (ref "J67") (pin "7") (pinfunction "7_7") (pintype "unspecified"))
      (node (ref "U14") (pin "8") (pinfunction "IO15_8") (pintype "unspecified"))
    )
    (net (code "31") (name "GPIO_36") (class "Default")
      (node (ref "OPT9") (pin "4") (pinfunction "4_4") (pintype "unspecified"))
      (node (ref "R78") (pin "1") (pinfunction "1_1") (pintype "unspecified"))
      (node (ref "R79") (pin "1") (pinfunction "1_1") (pintype "unspecified"))
      (node (ref "U14") (pin "29") (pinfunction "IO36_29") (pintype "unspecified"))
    )
    (net (code "32") (name "GPIO_37") (class "Default")
      (node (ref "OPT8") (pin "4") (pinfunction "4_4") (pintype "unspecified"))
      (node (ref "R72") (pin "1") (pinfunction "1_1") (pintype "unspecified"))
      (node (ref "R73") (pin "1") (pinfunction "1_1") (pintype "unspecified"))
      (node (ref "U14") (pin "30") (pinfunction "IO37_30") (pintype "unspecified"))
    )
    (net (code "33") (name "GPIO_38") (class "Default")
      (node (ref "OPT7") (pin "4") (pinfunction "4_4") (pintype "unspecified"))
      (node (ref "R65") (pin "1") (pinfunction "1_1") (pintype "unspecified"))
      (node (ref "R69") (pin "1") (pinfunction "1_1") (pintype "unspecified"))
      (node (ref "U14") (pin "31") (pinfunction "IO38_31") (pintype "unspecified"))
    )
    (net (code "34") (name "GPIO_39") (class "Default")
      (node (ref "OPT6") (pin "4") (pinfunction "4_4") (pintype "unspecified"))
      (node (ref "R62") (pin "1") (pinfunction "1_1") (pintype "unspecified"))
      (node (ref "R63") (pin "1") (pinfunction "1_1") (pintype "unspecified"))
      (node (ref "U14") (pin "32") (pinfunction "IO39_32") (pintype "unspecified"))
    )
    (net (code "35") (name "GPIO_40") (class "Default")
      (node (ref "OPT5") (pin "4") (pinfunction "4_4") (pintype "unspecified"))
      (node (ref "R56") (pin "1") (pinfunction "1_1") (pintype "unspecified"))
      (node (ref "R57") (pin "1") (pinfunction "1_1") (pintype "unspecified"))
      (node (ref "U14") (pin "33") (pinfunction "IO40_33") (pintype "unspecified"))
    )
    (net (code "36") (name "GPIO_41") (class "Default")
      (node (ref "OPT4") (pin "4") (pinfunction "4_4") (pintype "unspecified"))
      (node (ref "R49") (pin "1") (pinfunction "1_1") (pintype "unspecified"))
      (node (ref "R50") (pin "1") (pinfunction "1_1") (pintype "unspecified"))
      (node (ref "U14") (pin "34") (pinfunction "IO41_34") (pintype "unspecified"))
    )
    (net (code "37") (name "GPIO_42") (class "Default")
      (node (ref "OPT3") (pin "4") (pinfunction "4_4") (pintype "unspecified"))
      (node (ref "R107") (pin "1") (pinfunction "1_1") (pintype "unspecified"))
      (node (ref "R44") (pin "1") (pinfunction "1_1") (pintype "unspecified"))
      (node (ref "U14") (pin "35") (pinfunction "IO42_35") (pintype "unspecified"))
    )
    (net (code "38") (name "GPIO_45") (class "Default")
      (node (ref "R116") (pin "2") (pinfunction "2_2") (pintype "unspecified"))
      (node (ref "R6") (pin "2") (pinfunction "2_2") (pintype "input"))
      (node (ref "U14") (pin "26") (pinfunction "IO45_26") (pintype "unspecified"))
    )
    (net (code "39") (name "GPIO_46") (class "Default")
      (node (ref "R117") (pin "2") (pinfunction "2_2") (pintype "unspecified"))
      (node (ref "R9") (pin "2") (pinfunction "2_2") (pintype "input"))
      (node (ref "U14") (pin "16") (pinfunction "IO46_16") (pintype "unspecified"))
    )
    (net (code "40") (name "GPIO_47") (class "Default")
      (node (ref "OPT11") (pin "4") (pinfunction "4_4") (pintype "unspecified"))
      (node (ref "R93") (pin "1") (pinfunction "1_1") (pintype "unspecified"))
      (node (ref "R94") (pin "1") (pinfunction "1_1") (pintype "unspecified"))
      (node (ref "U14") (pin "24") (pinfunction "IO47_24") (pintype "unspecified"))
    )
    (net (code "41") (name "GPIO_48") (class "Default")
      (node (ref "OPT10") (pin "4") (pinfunction "4_4") (pintype "unspecified"))
      (node (ref "R81") (pin "1") (pinfunction "1_1") (pintype "unspecified"))
      (node (ref "R82") (pin "1") (pinfunction "1_1") (pintype "unspecified"))
      (node (ref "U14") (pin "25") (pinfunction "IO48_25") (pintype "unspecified"))
    )
    (net (code "42") (name "I2S_BCK") (class "Default")
      (node (ref "R71") (pin "2") (pinfunction "2_2") (pintype "input"))
      (node (ref "U10") (pin "11") (pinfunction "SHCP_11") (pintype "unspecified"))
      (node (ref "U11") (pin "11") (pinfunction "SHCP_11") (pintype "unspecified"))
      (node (ref "U14") (pin "9") (pinfunction "IO16_9") (pintype "unspecified"))
      (node (ref "U9") (pin "11") (pinfunction "SHCP_11") (pintype "unspecified"))
    )
    (net (code "43") (name "I2S_DATA") (class "Default")
      (node (ref "U14") (pin "10") (pinfunction "IO17_10") (pintype "unspecified"))
      (node (ref "U9") (pin "14") (pinfunction "DS_14") (pintype "unspecified"))
    )
    (net (code "44") (name "I2S_MR#") (class "Default")
      (node (ref "C30") (pin "2") (pinfunction "2_2") (pintype "unspecified"))
      (node (ref "R84") (pin "1") (pinfunction "1_1") (pintype "input"))
      (node (ref "U10") (pin "10") (pinfunction "MR#_10") (pintype "unspecified"))
      (node (ref "U11") (pin "10") (pinfunction "MR#_10") (pintype "unspecified"))
      (node (ref "U9") (pin "10") (pinfunction "MR#_10") (pintype "unspecified"))
    )
    (net (code "45") (name "I2S_WS") (class "Default")
      (node (ref "U10") (pin "12") (pinfunction "STCP_12") (pintype "unspecified"))
      (node (ref "U11") (pin "12") (pinfunction "STCP_12") (pintype "unspecified"))
      (node (ref "U14") (pin "11") (pinfunction "IO18_11") (pintype "unspecified"))
      (node (ref "U9") (pin "12") (pinfunction "STCP_12") (pintype "unspecified"))
    )
    (net (code "46") (name "MISO") (class "Default")
      (node (ref "SD1") (pin "7") (pinfunction "DAT0(D0)_7") (pintype "bidirectional"))
      (node (ref "U14") (pin "38") (pinfunction "IO2_38") (pintype "unspecified"))
    )
    (net (code "47") (name "MOSI") (class "Default")
      (node (ref "SD1") (pin "3") (pinfunction "CMD(DI)_3") (pintype "input"))
      (node (ref "U14") (pin "39") (pinfunction "IO1_39") (pintype "unspecified"))
    )
    (net (code "48") (name "Net-(C7-Pad2)") (class "Default")
      (node (ref "C7") (pin "2") (pinfunction "2_2") (pintype "input"))
      (node (ref "R4") (pin "1") (pinfunction "1_1") (pintype "input"))
    )
    (net (code "49") (name "Net-(D1-K)") (class "Default")
      (node (ref "C1") (pin "1") (pinfunction "1_1") (pintype "unspecified"))
      (node (ref "D1") (pin "1") (pinfunction "K_1") (pintype "unspecified"))
      (node (ref "L1") (pin "1") (pinfunction "1_1") (pintype "unspecified"))
      (node (ref "U1") (pin "8") (pinfunction "SW_8") (pintype "unspecified"))
    )
    (net (code "50") (name "Net-(D2-A)") (class "Default")
      (node (ref "D2") (pin "2") (pinfunction "A_2") (pintype "input"))
      (node (ref "Q1") (pin "1") (pinfunction "G_1") (pintype "unspecified"))
      (node (ref "R12") (pin "2") (pinfunction "2_2") (pintype "unspecified"))
    )
    (net (code "51") (name "Net-(D3-A)") (class "Default")
      (node (ref "D3") (pin "2") (pinfunction "A_2") (pintype "unspecified"))
      (node (ref "Q2") (pin "2") (pinfunction "D_2") (pintype "unspecified"))
      (node (ref "Q2") (pin "4") (pinfunction "D_4") (pintype "unspecified"))
      (node (ref "TB1") (pin "6") (pinfunction "6_6") (pintype "unspecified"))
    )
    (net (code "52") (name "Net-(D4-A)") (class "Default")
      (node (ref "D4") (pin "2") (pinfunction "A_2") (pintype "unspecified"))
      (node (ref "Q3") (pin "2") (pinfunction "D_2") (pintype "unspecified"))
      (node (ref "Q3") (pin "4") (pinfunction "D_4") (pintype "unspecified"))
      (node (ref "TB1") (pin "4") (pinfunction "4_4") (pintype "unspecified"))
    )
    (net (code "53") (name "Net-(D6-Pad2)") (class "Default")
      (node (ref "D6") (pin "2") (pinfunction "2_2") (pintype "unspecified"))
      (node (ref "R26") (pin "2") (pinfunction "2_2") (pintype "input"))
      (node (ref "RJ1") (pin "5") (pinfunction "5_5") (pintype "unspecified"))
    )
    (net (code "54") (name "Net-(D7-Pad2)") (class "Default")
      (node (ref "D7") (pin "2") (pinfunction "2_2") (pintype "unspecified"))
      (node (ref "R27") (pin "2") (pinfunction "2_2") (pintype "input"))
      (node (ref "RJ1") (pin "4") (pinfunction "4_4") (pintype "unspecified"))
    )
    (net (code "55") (name "Net-(D12-A)") (class "Default")
      (node (ref "D12") (pin "2") (pinfunction "A_2") (pintype "unspecified"))
      (node (ref "OPT3") (pin "2") (pinfunction "2_2") (pintype "unspecified"))
    )
    (net (code "56") (name "Net-(D12-K)") (class "Default")
      (node (ref "D12") (pin "1") (pinfunction "K_1") (pintype "unspecified"))
      (node (ref "J9") (pin "3") (pinfunction "3_3") (pintype "unspecified"))
    )
    (net (code "57") (name "Net-(D13-A)") (class "Default")
      (node (ref "D13") (pin "2") (pinfunction "A_2") (pintype "unspecified"))
      (node (ref "OPT4") (pin "2") (pinfunction "2_2") (pintype "unspecified"))
    )
    (net (code "58") (name "Net-(D13-K)") (class "Default")
      (node (ref "D13") (pin "1") (pinfunction "K_1") (pintype "unspecified"))
      (node (ref "J11") (pin "3") (pinfunction "3_3") (pintype "unspecified"))
    )
    (net (code "59") (name "Net-(D14-A)") (class "Default")
      (node (ref "D14") (pin "2") (pinfunction "A_2") (pintype "unspecified"))
      (node (ref "OPT5") (pin "2") (pinfunction "2_2") (pintype "unspecified"))
    )
    (net (code "60") (name "Net-(D14-K)") (class "Default")
      (node (ref "D14") (pin "1") (pinfunction "K_1") (pintype "unspecified"))
      (node (ref "J13") (pin "3") (pinfunction "3_3") (pintype "unspecified"))
    )
    (net (code "61") (name "Net-(D15-A)") (class "Default")
      (node (ref "D15") (pin "2") (pinfunction "A_2") (pintype "unspecified"))
      (node (ref "OPT6") (pin "2") (pinfunction "2_2") (pintype "unspecified"))
    )
    (net (code "62") (name "Net-(D15-K)") (class "Default")
      (node (ref "D15") (pin "1") (pinfunction "K_1") (pintype "unspecified"))
      (node (ref "J14") (pin "3") (pinfunction "3_3") (pintype "unspecified"))
    )
    (net (code "63") (name "Net-(D16-A)") (class "Default")
      (node (ref "D16") (pin "2") (pinfunction "A_2") (pintype "unspecified"))
      (node (ref "OPT7") (pin "2") (pinfunction "2_2") (pintype "unspecified"))
    )
    (net (code "64") (name "Net-(D16-K)") (class "Default")
      (node (ref "D16") (pin "1") (pinfunction "K_1") (pintype "unspecified"))
      (node (ref "J16") (pin "3") (pinfunction "3_3") (pintype "unspecified"))
    )
    (net (code "65") (name "Net-(D17-A)") (class "Default")
      (node (ref "D17") (pin "2") (pinfunction "A_2") (pintype "unspecified"))
      (node (ref "OPT8") (pin "2") (pinfunction "2_2") (pintype "unspecified"))
    )
    (net (code "66") (name "Net-(D17-K)") (class "Default")
      (node (ref "D17") (pin "1") (pinfunction "K_1") (pintype "unspecified"))
      (node (ref "J18") (pin "3") (pinfunction "3_3") (pintype "unspecified"))
    )
    (net (code "67") (name "Net-(D18-A)") (class "Default")
      (node (ref "D18") (pin "2") (pinfunction "A_2") (pintype "unspecified"))
      (node (ref "OPT9") (pin "2") (pinfunction "2_2") (pintype "unspecified"))
    )
    (net (code "68") (name "Net-(D18-K)") (class "Default")
      (node (ref "D18") (pin "1") (pinfunction "K_1") (pintype "unspecified"))
      (node (ref "J19") (pin "3") (pinfunction "3_3") (pintype "unspecified"))
    )
    (net (code "69") (name "Net-(D19-A)") (class "Default")
      (node (ref "D19") (pin "2") (pinfunction "A_2") (pintype "unspecified"))
      (node (ref "OPT10") (pin "2") (pinfunction "2_2") (pintype "unspecified"))
    )
    (net (code "70") (name "Net-(D19-K)") (class "Default")
      (node (ref "D19") (pin "1") (pinfunction "K_1") (pintype "unspecified"))
      (node (ref "J20") (pin "3") (pinfunction "3_3") (pintype "unspecified"))
    )
    (net (code "71") (name "Net-(D20-A)") (class "Default")
      (node (ref "D20") (pin "2") (pinfunction "A_2") (pintype "unspecified"))
      (node (ref "OPT11") (pin "2") (pinfunction "2_2") (pintype "unspecified"))
    )
    (net (code "72") (name "Net-(D20-K)") (class "Default")
      (node (ref "D20") (pin "1") (pinfunction "K_1") (pintype "unspecified"))
      (node (ref "J21") (pin "3") (pinfunction "3_3") (pintype "unspecified"))
    )
    (net (code "73") (name "Net-(D21-A)") (class "Default")
      (node (ref "D21") (pin "2") (pinfunction "A_2") (pintype "unspecified"))
      (node (ref "OPT12") (pin "2") (pinfunction "2_2") (pintype "unspecified"))
    )
    (net (code "74") (name "Net-(D21-K)") (class "Default")
      (node (ref "D21") (pin "1") (pinfunction "K_1") (pintype "unspecified"))
      (node (ref "J22") (pin "3") (pinfunction "3_3") (pintype "unspecified"))
    )
    (net (code "75") (name "Net-(D25-K)") (class "Default")
      (node (ref "D25") (pin "1") (pinfunction "K_1") (pintype "unspecified"))
      (node (ref "U13") (pin "1") (pinfunction "VIN_1") (pintype "unspecified"))
      (node (ref "U13") (pin "3") (pinfunction "ENABLE_3") (pintype "unspecified"))
    )
    (net (code "76") (name "Net-(H3-Pad2)") (class "Default")
      (node (ref "H3") (pin "2") (pinfunction "2_2") (pintype "unspecified"))
      (node (ref "PTC1") (pin "1") (pinfunction "1_1") (pintype "input"))
    )
    (net (code "77") (name "Net-(J7-Pad1)") (class "Default")
      (node (ref "J7") (pin "1") (pinfunction "1_1") (pintype "unspecified"))
      (node (ref "OPT2") (pin "4") (pinfunction "4_4") (pintype "unspecified"))
    )
    (net (code "78") (name "Net-(J7-Pad2)") (class "Default")
      (node (ref "J7") (pin "2") (pinfunction "2_2") (pintype "unspecified"))
      (node (ref "OPT1") (pin "4") (pinfunction "4_4") (pintype "unspecified"))
    )
    (net (code "79") (name "Net-(J7-Pad3)") (class "Default")
      (node (ref "J7") (pin "3") (pinfunction "3_3") (pintype "unspecified"))
      (node (ref "OPT1") (pin "3") (pinfunction "3_3") (pintype "unspecified"))
      (node (ref "OPT2") (pin "3") (pinfunction "3_3") (pintype "unspecified"))
    )
    (net (code "80") (name "Net-(LED2-K)") (class "Default")
      (node (ref "LED2") (pin "1") (pinfunction "K_1") (pintype "unspecified"))
      (node (ref "R114") (pin "2") (pinfunction "2_2") (pintype "input"))
    )
    (net (code "81") (name "Net-(LED8-A)") (class "Default")
      (node (ref "LED8") (pin "2") (pinfunction "A_2") (pintype "input"))
      (node (ref "R36") (pin "1") (pinfunction "1_1") (pintype "input"))
    )
    (net (code "82") (name "Net-(LED9-A)") (class "Default")
      (node (ref "LED9") (pin "2") (pinfunction "A_2") (pintype "input"))
      (node (ref "R37") (pin "1") (pinfunction "1_1") (pintype "input"))
    )
    (net (code "83") (name "Net-(LED10-A)") (class "Default")
      (node (ref "LED10") (pin "2") (pinfunction "A_2") (pintype "input"))
      (node (ref "R38") (pin "1") (pinfunction "1_1") (pintype "input"))
    )
    (net (code "84") (name "Net-(LED11-K)") (class "Default")
      (node (ref "LED11") (pin "1") (pinfunction "K_1") (pintype "unspecified"))
      (node (ref "R44") (pin "2") (pinfunction "2_2") (pintype "unspecified"))
    )
    (net (code "85") (name "Net-(LED12-A)") (class "Default")
      (node (ref "LED12") (pin "2") (pinfunction "A_2") (pintype "input"))
      (node (ref "R41") (pin "1") (pinfunction "1_1") (pintype "unspecified"))
    )
    (net (code "86") (name "Net-(LED13-A)") (class "Default")
      (node (ref "LED13") (pin "2") (pinfunction "A_2") (pintype "input"))
      (node (ref "R42") (pin "1") (pinfunction "1_1") (pintype "unspecified"))
    )
    (net (code "87") (name "Net-(LED14-A)") (class "Default")
      (node (ref "LED14") (pin "2") (pinfunction "A_2") (pintype "input"))
      (node (ref "R43") (pin "1") (pinfunction "1_1") (pintype "unspecified"))
    )
    (net (code "88") (name "Net-(LED15-K)") (class "Default")
      (node (ref "LED15") (pin "1") (pinfunction "K_1") (pintype "unspecified"))
      (node (ref "R49") (pin "2") (pinfunction "2_2") (pintype "unspecified"))
    )
    (net (code "89") (name "Net-(LED16-A)") (class "Default")
      (node (ref "LED16") (pin "2") (pinfunction "A_2") (pintype "input"))
      (node (ref "R51") (pin "1") (pinfunction "1_1") (pintype "unspecified"))
    )
    (net (code "90") (name "Net-(LED17-A)") (class "Default")
      (node (ref "LED17") (pin "2") (pinfunction "A_2") (pintype "input"))
      (node (ref "R52") (pin "1") (pinfunction "1_1") (pintype "unspecified"))
    )
    (net (code "91") (name "Net-(LED18-A)") (class "Default")
      (node (ref "LED18") (pin "2") (pinfunction "A_2") (pintype "input"))
      (node (ref "R53") (pin "1") (pinfunction "1_1") (pintype "unspecified"))
    )
    (net (code "92") (name "Net-(LED19-K)") (class "Default")
      (node (ref "LED19") (pin "1") (pinfunction "K_1") (pintype "unspecified"))
      (node (ref "R56") (pin "2") (pinfunction "2_2") (pintype "unspecified"))
    )
    (net (code "93") (name "Net-(LED20-K)") (class "Default")
      (node (ref "LED20") (pin "1") (pinfunction "K_1") (pintype "unspecified"))
      (node (ref "R62") (pin "2") (pinfunction "2_2") (pintype "unspecified"))
    )
    (net (code "94") (name "Net-(LED21-A)") (class "Default")
      (node (ref "LED21") (pin "2") (pinfunction "A_2") (pintype "input"))
      (node (ref "R59") (pin "1") (pinfunction "1_1") (pintype "unspecified"))
    )
    (net (code "95") (name "Net-(LED22-A)") (class "Default")
      (node (ref "LED22") (pin "2") (pinfunction "A_2") (pintype "input"))
      (node (ref "R60") (pin "1") (pinfunction "1_1") (pintype "unspecified"))
    )
    (net (code "96") (name "Net-(LED23-A)") (class "Default")
      (node (ref "LED23") (pin "2") (pinfunction "A_2") (pintype "input"))
      (node (ref "R61") (pin "1") (pinfunction "1_1") (pintype "unspecified"))
    )
    (net (code "97") (name "Net-(LED24-K)") (class "Default")
      (node (ref "LED24") (pin "1") (pinfunction "K_1") (pintype "unspecified"))
      (node (ref "R65") (pin "2") (pinfunction "2_2") (pintype "unspecified"))
    )
    (net (code "98") (name "Net-(LED25-A)") (class "Default")
      (node (ref "LED25") (pin "2") (pinfunction "A_2") (pintype "input"))
      (node (ref "R66") (pin "1") (pinfunction "1_1") (pintype "unspecified"))
    )
    (net (code "99") (name "Net-(LED26-A)") (class "Default")
      (node (ref "LED26") (pin "2") (pinfunction "A_2") (pintype "input"))
      (node (ref "R67") (pin "1") (pinfunction "1_1") (pintype "unspecified"))
    )
    (net (code "100") (name "Net-(LED27-A)") (class "Default")
      (node (ref "LED27") (pin "2") (pinfunction "A_2") (pintype "input"))
      (node (ref "R68") (pin "1") (pinfunction "1_1") (pintype "unspecified"))
    )
    (net (code "101") (name "Net-(LED28-K)") (class "Default")
      (node (ref "LED28") (pin "1") (pinfunction "K_1") (pintype "unspecified"))
      (node (ref "R72") (pin "2") (pinfunction "2_2") (pintype "unspecified"))
    )
    (net (code "102") (name "Net-(LED29-A)") (class "Default")
      (node (ref "LED29") (pin "2") (pinfunction "A_2") (pintype "input"))
      (node (ref "R75") (pin "1") (pinfunction "1_1") (pintype "unspecified"))
    )
    (net (code "103") (name "Net-(LED30-A)") (class "Default")
      (node (ref "LED30") (pin "2") (pinfunction "A_2") (pintype "input"))
      (node (ref "R76") (pin "1") (pinfunction "1_1") (pintype "unspecified"))
    )
    (net (code "104") (name "Net-(LED31-A)") (class "Default")
      (node (ref "LED31") (pin "2") (pinfunction "A_2") (pintype "input"))
      (node (ref "R77") (pin "1") (pinfunction "1_1") (pintype "unspecified"))
    )
    (net (code "105") (name "Net-(LED32-K)") (class "Default")
      (node (ref "LED32") (pin "1") (pinfunction "K_1") (pintype "unspecified"))
      (node (ref "R78") (pin "2") (pinfunction "2_2") (pintype "unspecified"))
    )
    (net (code "106") (name "Net-(LED33-K)") (class "Default")
      (node (ref "LED33") (pin "1") (pinfunction "K_1") (pintype "unspecified"))
      (node (ref "R81") (pin "2") (pinfunction "2_2") (pintype "unspecified"))
    )
    (net (code "107") (name "Net-(LED34-K)") (class "Default")
      (node (ref "LED34") (pin "1") (pinfunction "K_1") (pintype "unspecified"))
      (node (ref "R94") (pin "2") (pinfunction "2_2") (pintype "unspecified"))
    )
    (net (code "108") (name "Net-(LED35-K)") (class "Default")
      (node (ref "LED35") (pin "1") (pinfunction "K_1") (pintype "unspecified"))
      (node (ref "R96") (pin "2") (pinfunction "2_2") (pintype "unspecified"))
    )
    (net (code "109") (name "Net-(LED36-A)") (class "Default")
      (node (ref "LED36") (pin "2") (pinfunction "A_2") (pintype "input"))
      (node (ref "R99") (pin "1") (pinfunction "1_1") (pintype "unspecified"))
    )
    (net (code "110") (name "Net-(LED37-A)") (class "Default")
      (node (ref "LED37") (pin "2") (pinfunction "A_2") (pintype "input"))
      (node (ref "R100") (pin "1") (pinfunction "1_1") (pintype "unspecified"))
    )
    (net (code "111") (name "Net-(LED38-A)") (class "Default")
      (node (ref "LED38") (pin "2") (pinfunction "A_2") (pintype "input"))
      (node (ref "R101") (pin "1") (pinfunction "1_1") (pintype "unspecified"))
    )
    (net (code "112") (name "Net-(LED39-A)") (class "Default")
      (node (ref "LED39") (pin "2") (pinfunction "A_2") (pintype "input"))
      (node (ref "R102") (pin "1") (pinfunction "1_1") (pintype "unspecified"))
    )
    (net (code "113") (name "Net-(LED40-A)") (class "Default")
      (node (ref "LED40") (pin "2") (pinfunction "A_2") (pintype "input"))
      (node (ref "R103") (pin "1") (pinfunction "1_1") (pintype "unspecified"))
    )
    (net (code "114") (name "Net-(LED41-A)") (class "Default")
      (node (ref "LED41") (pin "2") (pinfunction "A_2") (pintype "input"))
      (node (ref "R104") (pin "1") (pinfunction "1_1") (pintype "unspecified"))
    )
    (net (code "115") (name "Net-(LED42-A)") (class "Default")
      (node (ref "J2") (pin "1") (pinfunction "1_1") (pintype "unspecified"))
      (node (ref "LED42") (pin "2") (pinfunction "A_2") (pintype "unspecified"))
      (node (ref "U2") (pin "6") (pinfunction "2Y_6") (pintype "unspecified"))
    )
    (net (code "116") (name "Net-(LED42-K)") (class "Default")
      (node (ref "LED42") (pin "1") (pinfunction "K_1") (pintype "unspecified"))
      (node (ref "R110") (pin "1") (pinfunction "1_1") (pintype "unspecified"))
    )
    (net (code "117") (name "Net-(LED43-A)") (class "Default")
      (node (ref "J4") (pin "1") (pinfunction "1_1") (pintype "unspecified"))
      (node (ref "LED43") (pin "2") (pinfunction "A_2") (pintype "unspecified"))
      (node (ref "U2") (pin "8") (pinfunction "3Y_8") (pintype "unspecified"))
    )
    (net (code "118") (name "Net-(LED43-K)") (class "Default")
      (node (ref "LED43") (pin "1") (pinfunction "K_1") (pintype "unspecified"))
      (node (ref "R111") (pin "1") (pinfunction "1_1") (pintype "unspecified"))
    )
    (net (code "119") (name "Net-(LED44-A)") (class "Default")
      (node (ref "J3") (pin "1") (pinfunction "1_1") (pintype "unspecified"))
      (node (ref "LED44") (pin "2") (pinfunction "A_2") (pintype "unspecified"))
      (node (ref "U2") (pin "11") (pinfunction "4Y_11") (pintype "unspecified"))
    )
    (net (code "120") (name "Net-(LED44-K)") (class "Default")
      (node (ref "LED44") (pin "1") (pinfunction "K_1") (pintype "unspecified"))
      (node (ref "R112") (pin "1") (pinfunction "1_1") (pintype "unspecified"))
    )
    (net (code "121") (name "Net-(LED45-A)") (class "Default")
      (node (ref "J1") (pin "1") (pinfunction "1_1") (pintype "unspecified"))
      (node (ref "LED45") (pin "2") (pinfunction "A_2") (pintype "unspecified"))
      (node (ref "U2") (pin "3") (pinfunction "1Y_3") (pintype "unspecified"))
    )
    (net (code "122") (name "Net-(LED45-K)") (class "Default")
      (node (ref "LED45") (pin "1") (pinfunction "K_1") (pintype "unspecified"))
      (node (ref "R113") (pin "1") (pinfunction "1_1") (pintype "unspecified"))
    )
    (net (code "123") (name "Net-(LED46-K)") (class "Default")
      (node (ref "LED46") (pin "1") (pinfunction "K_1") (pintype "input"))
      (node (ref "R115") (pin "2") (pinfunction "2_2") (pintype "input"))
    )
    (net (code "124") (name "Net-(LED47-K)") (class "Default")
      (node (ref "LED47") (pin "1") (pinfunction "K_1") (pintype "input"))
      (node (ref "R1") (pin "2") (pinfunction "2_2") (pintype "unspecified"))
    )
    (net (code "125") (name "Net-(OPT1-Pad1)") (class "Default")
      (node (ref "OPT1") (pin "1") (pinfunction "1_1") (pintype "unspecified"))
      (node (ref "R39") (pin "2") (pinfunction "2_2") (pintype "input"))
    )
    (net (code "126") (name "Net-(OPT2-Pad1)") (class "Default")
      (node (ref "OPT2") (pin "1") (pinfunction "1_1") (pintype "unspecified"))
      (node (ref "R40") (pin "2") (pinfunction "2_2") (pintype "input"))
    )
    (net (code "127") (name "Net-(OPT3-Pad1)") (class "Default")
      (node (ref "OPT3") (pin "1") (pinfunction "1_1") (pintype "unspecified"))
      (node (ref "R85") (pin "2") (pinfunction "2_2") (pintype "input"))
    )
    (net (code "128") (name "Net-(OPT4-Pad1)") (class "Default")
      (node (ref "OPT4") (pin "1") (pinfunction "1_1") (pintype "unspecified"))
      (node (ref "R86") (pin "2") (pinfunction "2_2") (pintype "input"))
    )
    (net (code "129") (name "Net-(OPT5-Pad1)") (class "Default")
      (node (ref "OPT5") (pin "1") (pinfunction "1_1") (pintype "unspecified"))
      (node (ref "R87") (pin "2") (pinfunction "2_2") (pintype "input"))
    )
    (net (code "130") (name "Net-(OPT6-Pad1)") (class "Default")
      (node (ref "OPT6") (pin "1") (pinfunction "1_1") (pintype "unspecified"))
      (node (ref "R88") (pin "2") (pinfunction "2_2") (pintype "input"))
    )
    (net (code "131") (name "Net-(OPT7-Pad1)") (class "Default")
      (node (ref "OPT7") (pin "1") (pinfunction "1_1") (pintype "unspecified"))
      (node (ref "R89") (pin "2") (pinfunction "2_2") (pintype "input"))
    )
    (net (code "132") (name "Net-(OPT8-Pad1)") (class "Default")
      (node (ref "OPT8") (pin "1") (pinfunction "1_1") (pintype "unspecified"))
      (node (ref "R90") (pin "2") (pinfunction "2_2") (pintype "input"))
    )
    (net (code "133") (name "Net-(OPT9-Pad1)") (class "Default")
      (node (ref "OPT9") (pin "1") (pinfunction "1_1") (pintype "unspecified"))
      (node (ref "R91") (pin "2") (pinfunction "2_2") (pintype "input"))
    )
    (net (code "134") (name "Net-(OPT10-Pad1)") (class "Default")
      (node (ref "OPT10") (pin "1") (pinfunction "1_1") (pintype "unspecified"))
      (node (ref "R92") (pin "2") (pinfunction "2_2") (pintype "input"))
    )
    (net (code "135") (name "Net-(OPT11-Pad1)") (class "Default")
      (node (ref "OPT11") (pin "1") (pinfunction "1_1") (pintype "unspecified"))
      (node (ref "R97") (pin "2") (pinfunction "2_2") (pintype "input"))
    )
    (net (code "136") (name "Net-(OPT12-Pad1)") (class "Default")
      (node (ref "OPT12") (pin "1") (pinfunction "1_1") (pintype "unspecified"))
      (node (ref "R98") (pin "2") (pinfunction "2_2") (pintype "input"))
    )
    (net (code "137") (name "Net-(Q2-G)") (class "Default")
      (node (ref "Q2") (pin "1") (pinfunction "G_1") (pintype "unspecified"))
      (node (ref "R11") (pin "2") (pinfunction "2_2") (pintype "input"))
    )
    (net (code "138") (name "Net-(Q3-G)") (class "Default")
      (node (ref "Q3") (pin "1") (pinfunction "G_1") (pintype "unspecified"))
      (node (ref "R16") (pin "2") (pinfunction "2_2") (pintype "input"))
    )
    (net (code "139") (name "Net-(Q4-D)") (class "Default")
      (node (ref "Q4") (pin "3") (pinfunction "D_3") (pintype "unspecified"))
      (node (ref "R13") (pin "1") (pinfunction "1_1") (pintype "input"))
      (node (ref "U5") (pin "2") (pinfunction "nRE_2") (pintype "unspecified"))
      (node (ref "U5") (pin "3") (pinfunction "DE_3") (pintype "unspecified"))
    )
    (net (code "140") (name "Net-(Q4-G)") (class "Default")
      (node (ref "Q4") (pin "1") (pinfunction "G_1") (pintype "unspecified"))
      (node (ref "R19") (pin "1") (pinfunction "1_1") (pintype "input"))
    )
    (net (code "141") (name "Net-(Q5-B)") (class "Default")
      (node (ref "Q5") (pin "1") (pinfunction "B_1") (pintype "unspecified"))
      (node (ref "R28") (pin "2") (pinfunction "2_2") (pintype "input"))
    )
    (net (code "142") (name "Net-(Q6-B)") (class "Default")
      (node (ref "Q6") (pin "1") (pinfunction "B_1") (pintype "unspecified"))
      (node (ref "R29") (pin "2") (pinfunction "2_2") (pintype "input"))
    )
    (net (code "143") (name "Net-(R31-Pad2)") (class "Default")
      (node (ref "R31") (pin "2") (pinfunction "2_2") (pintype "input"))
      (node (ref "SW1") (pin "1") (pinfunction "1_1") (pintype "unspecified"))
    )
    (net (code "144") (name "Net-(R33-Pad2)") (class "Default")
      (node (ref "R33") (pin "2") (pinfunction "2_2") (pintype "input"))
      (node (ref "SW2") (pin "1") (pinfunction "1_1") (pintype "unspecified"))
    )
    (net (code "145") (name "Net-(R47-Pad2)") (class "Default")
      (node (ref "R47") (pin "2") (pinfunction "2_2") (pintype "input"))
      (node (ref "VR1") (pin "1") (pinfunction "1_1") (pintype "unspecified"))
    )
    (net (code "146") (name "Net-(U1-BOOT)") (class "Default")
      (node (ref "C1") (pin "2") (pinfunction "2_2") (pintype "unspecified"))
      (node (ref "U1") (pin "1") (pinfunction "BOOT_1") (pintype "unspecified"))
    )
    (net (code "147") (name "Net-(U1-COMP)") (class "Default")
      (node (ref "C6") (pin "2") (pinfunction "2_2") (pintype "input"))
      (node (ref "R4") (pin "2") (pinfunction "2_2") (pintype "input"))
      (node (ref "U1") (pin "6") (pinfunction "COMP_6") (pintype "unspecified"))
    )
    (net (code "148") (name "Net-(U1-FB)") (class "Default")
      (node (ref "R120") (pin "2") (pinfunction "2_2") (pintype "unspecified"))
      (node (ref "R121") (pin "1") (pinfunction "1_1") (pintype "input"))
      (node (ref "U1") (pin "5") (pinfunction "FB_5") (pintype "unspecified"))
    )
    (net (code "149") (name "Net-(U1-RT{slash}CLK)") (class "Default")
      (node (ref "R3") (pin "2") (pinfunction "2_2") (pintype "input"))
      (node (ref "U1") (pin "4") (pinfunction "RT/CLK_4") (pintype "unspecified"))
    )
    (net (code "150") (name "Net-(U2-1A)") (class "Default")
      (node (ref "R5") (pin "2") (pinfunction "2_2") (pintype "input"))
      (node (ref "U2") (pin "2") (pinfunction "1A_2") (pintype "unspecified"))
    )
    (net (code "151") (name "Net-(U2-2A)") (class "Default")
      (node (ref "R8") (pin "2") (pinfunction "2_2") (pintype "input"))
      (node (ref "U2") (pin "5") (pinfunction "2A_5") (pintype "unspecified"))
    )
    (net (code "152") (name "Net-(U2-3A)") (class "Default")
      (node (ref "R9") (pin "1") (pinfunction "1_1") (pintype "input"))
      (node (ref "U2") (pin "9") (pinfunction "3A_9") (pintype "unspecified"))
    )
    (net (code "153") (name "Net-(U2-4A)") (class "Default")
      (node (ref "R6") (pin "1") (pinfunction "1_1") (pintype "input"))
      (node (ref "U2") (pin "12") (pinfunction "4A_12") (pintype "unspecified"))
    )
    (net (code "154") (name "Net-(U4-VIA)") (class "Default")
      (node (ref "R17") (pin "1") (pinfunction "1_1") (pintype "input"))
      (node (ref "U4") (pin "7") (pinfunction "VIA_7") (pintype "unspecified"))
    )
    (net (code "155") (name "Net-(U4-VOB)") (class "Default")
      (node (ref "R19") (pin "2") (pinfunction "2_2") (pintype "input"))
      (node (ref "U4") (pin "6") (pinfunction "VOB_6") (pintype "output"))
      (node (ref "U5") (pin "4") (pinfunction "D_4") (pintype "unspecified"))
    )
    (net (code "156") (name "Net-(U5-A)") (class "Default")
      (node (ref "D5") (pin "1") (pinfunction "1_1") (pintype "unspecified"))
      (node (ref "J5") (pin "1") (pinfunction "1_1") (pintype "unspecified"))
      (node (ref "R15") (pin "1") (pinfunction "1_1") (pintype "input"))
      (node (ref "R18") (pin "1") (pinfunction "1_1") (pintype "input"))
      (node (ref "U5") (pin "6") (pinfunction "A_6") (pintype "unspecified"))
    )
    (net (code "157") (name "Net-(U5-B)") (class "Default")
      (node (ref "D5") (pin "2") (pinfunction "2_2") (pintype "unspecified"))
      (node (ref "J5") (pin "2") (pinfunction "2_2") (pintype "unspecified"))
      (node (ref "R18") (pin "2") (pinfunction "2_2") (pintype "input"))
      (node (ref "R20") (pin "2") (pinfunction "2_2") (pintype "input"))
      (node (ref "U5") (pin "7") (pinfunction "B_7") (pintype "unspecified"))
    )
    (net (code "158") (name "Net-(U5-R)") (class "Default")
      (node (ref "R17") (pin "2") (pinfunction "2_2") (pintype "input"))
      (node (ref "U5") (pin "1") (pinfunction "R_1") (pintype "unspecified"))
    )
    (net (code "159") (name "Net-(U7-D+)") (class "Default")
      (node (ref "D10") (pin "2") (pinfunction "2_2") (pintype "unspecified"))
      (node (ref "U7") (pin "4") (pinfunction "D+_4") (pintype "unspecified"))
      (node (ref "USB1") (pin "6") (pinfunction "DP1_6") (pintype "unspecified"))
      (node (ref "USB1") (pin "8") (pinfunction "DP2_8") (pintype "unspecified"))
    )
    (net (code "160") (name "Net-(U7-D-)") (class "Default")
      (node (ref "D9") (pin "2") (pinfunction "2_2") (pintype "unspecified"))
      (node (ref "U7") (pin "5") (pinfunction "D-_5") (pintype "unspecified"))
      (node (ref "USB1") (pin "5") (pinfunction "DN2_5") (pintype "unspecified"))
      (node (ref "USB1") (pin "7") (pinfunction "DN1_7") (pintype "unspecified"))
    )
    (net (code "161") (name "Net-(U7-VDD)") (class "Default")
      (node (ref "C21") (pin "2") (pinfunction "2_2") (pintype "input"))
      (node (ref "C22") (pin "1") (pinfunction "1_1") (pintype "unspecified"))
      (node (ref "U7") (pin "6") (pinfunction "VDD_6") (pintype "unspecified"))
    )
    (net (code "162") (name "Net-(U8-IN1+)") (class "Default")
      (node (ref "C25") (pin "2") (pinfunction "2_2") (pintype "unspecified"))
      (node (ref "R48") (pin "2") (pinfunction "2_2") (pintype "input"))
      (node (ref "U8") (pin "3") (pinfunction "IN1+_3") (pintype "unspecified"))
    )
    (net (code "163") (name "Net-(U8-IN1-)") (class "Default")
      (node (ref "R47") (pin "1") (pinfunction "1_1") (pintype "input"))
      (node (ref "R54") (pin "2") (pinfunction "2_2") (pintype "input"))
      (node (ref "U8") (pin "2") (pinfunction "IN1-_2") (pintype "unspecified"))
    )
    (net (code "164") (name "Net-(U8-IN2-)") (class "Default")
      (node (ref "U8") (pin "6") (pinfunction "IN2-_6") (pintype "unspecified"))
      (node (ref "U8") (pin "7") (pinfunction "OUT2_7") (pintype "unspecified"))
    )
    (net (code "165") (name "Net-(U8-OUT1)") (class "Default")
      (node (ref "J7") (pin "4") (pinfunction "4_4") (pintype "unspecified"))
      (node (ref "U8") (pin "1") (pinfunction "OUT1_1") (pintype "unspecified"))
      (node (ref "VR1") (pin "2") (pinfunction "2_2") (pintype "unspecified"))
    )
    (net (code "166") (name "Net-(U10-DS)") (class "Default")
      (node (ref "U10") (pin "14") (pinfunction "DS_14") (pintype "unspecified"))
      (node (ref "U9") (pin "9") (pinfunction "Q7S_9") (pintype "unspecified"))
    )
    (net (code "167") (name "Net-(U10-Q7S)") (class "Default")
      (node (ref "U10") (pin "9") (pinfunction "Q7S_9") (pintype "unspecified"))
      (node (ref "U11") (pin "14") (pinfunction "DS_14") (pintype "unspecified"))
    )
    (net (code "168") (name "Net-(U13-VOUT)") (class "Default")
      (node (ref "D22") (pin "2") (pinfunction "2_2") (pintype "unspecified"))
      (node (ref "U13") (pin "5") (pinfunction "VOUT_5") (pintype "unspecified"))
      (node (ref "USB2") (pin "11") (pinfunction "VBUS_11") (pintype "unspecified"))
      (node (ref "USB2") (pin "2") (pinfunction "VBUS_2") (pintype "unspecified"))
    )
    (net (code "169") (name "Net-(USB1-CC1)") (class "Default")
      (node (ref "R35") (pin "2") (pinfunction "2_2") (pintype "input"))
      (node (ref "USB1") (pin "4") (pinfunction "CC1_4") (pintype "unspecified"))
    )
    (net (code "170") (name "Net-(USB1-CC2)") (class "Default")
      (node (ref "R34") (pin "2") (pinfunction "2_2") (pintype "input"))
      (node (ref "USB1") (pin "10") (pinfunction "CC2_10") (pintype "unspecified"))
    )
    (net (code "171") (name "Net-(USB2-CC1)") (class "Default")
      (node (ref "R106") (pin "2") (pinfunction "2_2") (pintype "input"))
      (node (ref "USB2") (pin "4") (pinfunction "CC1_4") (pintype "unspecified"))
    )
    (net (code "172") (name "Net-(USB2-CC2)") (class "Default")
      (node (ref "R105") (pin "2") (pinfunction "2_2") (pintype "input"))
      (node (ref "USB2") (pin "10") (pinfunction "CC2_10") (pintype "unspecified"))
    )
    (net (code "173") (name "RS485_RX") (class "Default")
      (node (ref "R114") (pin "1") (pinfunction "1_1") (pintype "input"))
      (node (ref "U14") (pin "19") (pinfunction "IO11_19") (pintype "unspecified"))
      (node (ref "U4") (pin "2") (pinfunction "VOA_2") (pintype "output"))
    )
    (net (code "174") (name "RS485_TX") (class "Default")
      (node (ref "R115") (pin "1") (pinfunction "1_1") (pintype "input"))
      (node (ref "U14") (pin "20") (pinfunction "IO12_20") (pintype "unspecified"))
      (node (ref "U4") (pin "3") (pinfunction "VIB_3") (pintype "unspecified"))
    )
    (net (code "175") (name "RTS") (class "Default")
      (node (ref "Q5") (pin "2") (pinfunction "E_2") (pintype "unspecified"))
      (node (ref "R29") (pin "1") (pinfunction "1_1") (pintype "input"))
      (node (ref "U7") (pin "24") (pinfunction "RTS_24") (pintype "unspecified"))
    )
    (net (code "176") (name "SCK") (class "Default")
      (node (ref "SD1") (pin "5") (pinfunction "CLK(SCLK)_5") (pintype "input"))
      (node (ref "U14") (pin "23") (pinfunction "IO21_23") (pintype "unspecified"))
    )
    (net (code "177") (name "SW_VCC") (class "Default")
      (node (ref "J11") (pin "1") (pinfunction "1_1") (pintype "unspecified"))
      (node (ref "J13") (pin "1") (pinfunction "1_1") (pintype "unspecified"))
      (node (ref "J14") (pin "1") (pinfunction "1_1") (pintype "unspecified"))
      (node (ref "J16") (pin "1") (pinfunction "1_1") (pintype "unspecified"))
      (node (ref "J18") (pin "1") (pinfunction "1_1") (pintype "unspecified"))
      (node (ref "J19") (pin "1") (pinfunction "1_1") (pintype "unspecified"))
      (node (ref "J20") (pin "1") (pinfunction "1_1") (pintype "unspecified"))
      (node (ref "J21") (pin "1") (pinfunction "1_1") (pintype "unspecified"))
      (node (ref "J22") (pin "1") (pinfunction "1_1") (pintype "unspecified"))
      (node (ref "J9") (pin "1") (pinfunction "1_1") (pintype "unspecified"))
      (node (ref "PTC1") (pin "2") (pinfunction "2_2") (pintype "input"))
      (node (ref "R85") (pin "1") (pinfunction "1_1") (pintype "input"))
      (node (ref "R86") (pin "1") (pinfunction "1_1") (pintype "input"))
      (node (ref "R87") (pin "1") (pinfunction "1_1") (pintype "input"))
      (node (ref "R88") (pin "1") (pinfunction "1_1") (pintype "input"))
      (node (ref "R89") (pin "1") (pinfunction "1_1") (pintype "input"))
      (node (ref "R90") (pin "1") (pinfunction "1_1") (pintype "input"))
      (node (ref "R91") (pin "1") (pinfunction "1_1") (pintype "input"))
      (node (ref "R92") (pin "1") (pinfunction "1_1") (pintype "input"))
      (node (ref "R97") (pin "1") (pinfunction "1_1") (pintype "input"))
      (node (ref "R98") (pin "1") (pinfunction "1_1") (pintype "input"))
    )
    (net (code "178") (name "U0RXD_GPIO_44") (class "Default")
      (node (ref "U14") (pin "36") (pinfunction "RXD0_36") (pintype "unspecified"))
      (node (ref "U7") (pin "26") (pinfunction "TXD_26") (pintype "unspecified"))
    )
    (net (code "179") (name "U0TDX_GPIO_43") (class "Default")
      (node (ref "U14") (pin "37") (pinfunction "TXD0_37") (pintype "unspecified"))
      (node (ref "U7") (pin "25") (pinfunction "RXD_25") (pintype "unspecified"))
    )
    (net (code "180") (name "USB_D+") (class "Default")
      (node (ref "D23") (pin "2") (pinfunction "2_2") (pintype "unspecified"))
      (node (ref "U14") (pin "14") (pinfunction "IO20_14") (pintype "unspecified"))
      (node (ref "USB2") (pin "6") (pinfunction "DP1_6") (pintype "unspecified"))
      (node (ref "USB2") (pin "8") (pinfunction "DP2_8") (pintype "unspecified"))
    )
    (net (code "181") (name "USB_D-") (class "Default")
      (node (ref "D24") (pin "2") (pinfunction "2_2") (pintype "unspecified"))
      (node (ref "U14") (pin "13") (pinfunction "IO19_13") (pintype "unspecified"))
      (node (ref "USB2") (pin "5") (pinfunction "DN2_5") (pintype "unspecified"))
      (node (ref "USB2") (pin "7") (pinfunction "DN1_7") (pintype "unspecified"))
    )
    (net (code "182") (name "U_DIR") (class "Default")
      (node (ref "J23") (pin "3") (pinfunction "3_3") (pintype "unspecified"))
      (node (ref "R101") (pin "2") (pinfunction "2_2") (pintype "unspecified"))
      (node (ref "U11") (pin "3") (pinfunction "Q3_3") (pintype "unspecified"))
    )
    (net (code "183") (name "U_ENABLE") (class "Default")
      (node (ref "J23") (pin "5") (pinfunction "5_5") (pintype "unspecified"))
      (node (ref "R99") (pin "2") (pinfunction "2_2") (pintype "unspecified"))
      (node (ref "U11") (pin "4") (pinfunction "Q4_4") (pintype "unspecified"))
    )
    (net (code "184") (name "U_STEP") (class "Default")
      (node (ref "J23") (pin "4") (pinfunction "4_4") (pintype "unspecified"))
      (node (ref "R100") (pin "2") (pinfunction "2_2") (pintype "unspecified"))
      (node (ref "U11") (pin "2") (pinfunction "Q2_2") (pintype "unspecified"))
    )
    (net (code "185") (name "VBUS") (class "Default")
      (node (ref "C23") (pin "2") (pinfunction "2_2") (pintype "input"))
      (node (ref "C24") (pin "1") (pinfunction "1_1") (pintype "unspecified"))
      (node (ref "D11") (pin "2") (pinfunction "2_2") (pintype "unspecified"))
      (node (ref "U7") (pin "8") (pinfunction "VBUS_8") (pintype "unspecified"))
      (node (ref "USB1") (pin "11") (pinfunction "VBUS_11") (pintype "unspecified"))
      (node (ref "USB1") (pin "2") (pinfunction "VBUS_2") (pintype "unspecified"))
    )
    (net (code "186") (name "VIN") (class "Default")
      (node (ref "Q1") (pin "4") (pinfunction "D_4") (pintype "unspecified"))
      (node (ref "TB1") (pin "1") (pinfunction "1_1") (pintype "unspecified"))
    )
    (net (code "187") (name "V_DIR") (class "Default")
      (node (ref "J24") (pin "3") (pinfunction "3_3") (pintype "unspecified"))
      (node (ref "R104") (pin "2") (pinfunction "2_2") (pintype "unspecified"))
      (node (ref "U11") (pin "6") (pinfunction "Q6_6") (pintype "unspecified"))
    )
    (net (code "188") (name "V_ENABLE") (class "Default")
      (node (ref "J24") (pin "5") (pinfunction "5_5") (pintype "unspecified"))
      (node (ref "R102") (pin "2") (pinfunction "2_2") (pintype "unspecified"))
      (node (ref "U11") (pin "7") (pinfunction "Q7_7") (pintype "unspecified"))
    )
    (net (code "189") (name "V_STEP") (class "Default")
      (node (ref "J24") (pin "4") (pinfunction "4_4") (pintype "unspecified"))
      (node (ref "R103") (pin "2") (pinfunction "2_2") (pintype "unspecified"))
      (node (ref "U11") (pin "5") (pinfunction "Q5_5") (pintype "unspecified"))
    )
    (net (code "190") (name "X_DIR") (class "Default")
      (node (ref "J6") (pin "3") (pinfunction "3_3") (pintype "unspecified"))
      (node (ref "R38") (pin "2") (pinfunction "2_2") (pintype "input"))
      (node (ref "U9") (pin "1") (pinfunction "Q1_1") (pintype "unspecified"))
    )
    (net (code "191") (name "X_ENABLE") (class "Default")
      (node (ref "J6") (pin "5") (pinfunction "5_5") (pintype "unspecified"))
      (node (ref "R36") (pin "2") (pinfunction "2_2") (pintype "input"))
      (node (ref "U9") (pin "2") (pinfunction "Q2_2") (pintype "unspecified"))
    )
    (net (code "192") (name "X_STEP") (class "Default")
      (node (ref "J6") (pin "4") (pinfunction "4_4") (pintype "unspecified"))
      (node (ref "R37") (pin "2") (pinfunction "2_2") (pintype "input"))
      (node (ref "U9") (pin "15") (pinfunction "Q0_15") (pintype "unspecified"))
    )
    (net (code "193") (name "Y_DIR") (class "Default")
      (node (ref "J8") (pin "3") (pinfunction "3_3") (pintype "unspecified"))
      (node (ref "R43") (pin "2") (pinfunction "2_2") (pintype "unspecified"))
      (node (ref "U9") (pin "4") (pinfunction "Q4_4") (pintype "unspecified"))
    )
    (net (code "194") (name "Y_ENABLE") (class "Default")
      (node (ref "J8") (pin "5") (pinfunction "5_5") (pintype "unspecified"))
      (node (ref "R41") (pin "2") (pinfunction "2_2") (pintype "unspecified"))
      (node (ref "U9") (pin "5") (pinfunction "Q5_5") (pintype "unspecified"))
    )
    (net (code "195") (name "Y_STEP") (class "Default")
      (node (ref "J8") (pin "4") (pinfunction "4_4") (pintype "unspecified"))
      (node (ref "R42") (pin "2") (pinfunction "2_2") (pintype "unspecified"))
      (node (ref "U9") (pin "3") (pinfunction "Q3_3") (pintype "unspecified"))
    )
    (net (code "196") (name "Z_DIR") (class "Default")
      (node (ref "J10") (pin "3") (pinfunction "3_3") (pintype "unspecified"))
      (node (ref "R53") (pin "2") (pinfunction "2_2") (pintype "unspecified"))
      (node (ref "U9") (pin "7") (pinfunction "Q7_7") (pintype "unspecified"))
    )
    (net (code "197") (name "Z_ENABLE") (class "Default")
      (node (ref "J10") (pin "5") (pinfunction "5_5") (pintype "unspecified"))
      (node (ref "R51") (pin "2") (pinfunction "2_2") (pintype "unspecified"))
      (node (ref "U10") (pin "15") (pinfunction "Q0_15") (pintype "unspecified"))
    )
    (net (code "198") (name "Z_STEP") (class "Default")
      (node (ref "J10") (pin "4") (pinfunction "4_4") (pintype "unspecified"))
      (node (ref "R52") (pin "2") (pinfunction "2_2") (pintype "unspecified"))
      (node (ref "U9") (pin "6") (pinfunction "Q6_6") (pintype "unspecified"))
    )
    (net (code "199") (name "unconnected-(J67-Pad8)") (class "Default")
      (node (ref "J67") (pin "8") (pinfunction "8_8") (pintype "unspecified+no_connect"))
    )
    (net (code "200") (name "unconnected-(J67-Pad9)") (class "Default")
      (node (ref "J67") (pin "9") (pinfunction "9_9") (pintype "unspecified+no_connect"))
    )
    (net (code "201") (name "unconnected-(J67-Pad10)") (class "Default")
      (node (ref "J67") (pin "10") (pinfunction "10_10") (pintype "unspecified+no_connect"))
    )
    (net (code "202") (name "unconnected-(J67-Pad11)") (class "Default")
      (node (ref "J67") (pin "11") (pinfunction "11_11") (pintype "unspecified+no_connect"))
    )
    (net (code "203") (name "unconnected-(MH5-Pad1)") (class "Default")
      (node (ref "MH5") (pin "1") (pinfunction "1_1") (pintype "unspecified+no_connect"))
    )
    (net (code "204") (name "unconnected-(PS1-NC-Pad8)") (class "Default")
      (node (ref "PS1") (pin "8") (pinfunction "NC_8") (pintype "unspecified+no_connect"))
    )
    (net (code "205") (name "unconnected-(SD1-CD-Pad9)") (class "Default")
      (node (ref "SD1") (pin "9") (pinfunction "CD_9") (pintype "input+no_connect"))
    )
    (net (code "206") (name "unconnected-(SD1-DAT1(RSV)-Pad8)") (class "Default")
      (node (ref "SD1") (pin "8") (pinfunction "DAT1(RSV)_8") (pintype "bidirectional+no_connect"))
    )
    (net (code "207") (name "unconnected-(SD1-DAT2(RSV)-Pad1)") (class "Default")
      (node (ref "SD1") (pin "1") (pinfunction "DAT2(RSV)_1") (pintype "bidirectional+no_connect"))
    )
    (net (code "208") (name "unconnected-(U1-EN-Pad3)") (class "Default")
      (node (ref "U1") (pin "3") (pinfunction "EN_3") (pintype "unspecified+no_connect"))
    )
    (net (code "209") (name "unconnected-(U3-Output-Pad4)") (class "Default")
      (node (ref "U3") (pin "4") (pinfunction "Output_4") (pintype "unspecified+no_connect"))
    )
    (net (code "210") (name "unconnected-(U7-CTS-Pad23)") (class "Default")
      (node (ref "U7") (pin "23") (pinfunction "CTS_23") (pintype "unspecified+no_connect"))
    )
    (net (code "211") (name "unconnected-(U7-DCD-Pad1)") (class "Default")
      (node (ref "U7") (pin "1") (pinfunction "DCD_1") (pintype "unspecified+no_connect"))
    )
    (net (code "212") (name "unconnected-(U7-DSR-Pad27)") (class "Default")
      (node (ref "U7") (pin "27") (pinfunction "DSR_27") (pintype "unspecified+no_connect"))
    )
    (net (code "213") (name "unconnected-(U7-NC-Pad10)") (class "Default")
      (node (ref "U7") (pin "10") (pinfunction "NC_10") (pintype "unspecified+no_connect"))
    )
    (net (code "214") (name "unconnected-(U7-NC-Pad13)") (class "Default")
      (node (ref "U7") (pin "13") (pinfunction "NC_13") (pintype "unspecified+no_connect"))
    )
    (net (code "215") (name "unconnected-(U7-NC-Pad14)") (class "Default")
      (node (ref "U7") (pin "14") (pinfunction "NC_14") (pintype "unspecified+no_connect"))
    )
    (net (code "216") (name "unconnected-(U7-NC-Pad15)") (class "Default")
      (node (ref "U7") (pin "15") (pinfunction "NC_15") (pintype "unspecified+no_connect"))
    )
    (net (code "217") (name "unconnected-(U7-NC-Pad16)") (class "Default")
      (node (ref "U7") (pin "16") (pinfunction "NC_16") (pintype "unspecified+no_connect"))
    )
    (net (code "218") (name "unconnected-(U7-NC-Pad17)") (class "Default")
      (node (ref "U7") (pin "17") (pinfunction "NC_17") (pintype "unspecified+no_connect"))
    )
    (net (code "219") (name "unconnected-(U7-NC-Pad18)") (class "Default")
      (node (ref "U7") (pin "18") (pinfunction "NC_18") (pintype "unspecified+no_connect"))
    )
    (net (code "220") (name "unconnected-(U7-NC-Pad19)") (class "Default")
      (node (ref "U7") (pin "19") (pinfunction "NC_19") (pintype "unspecified+no_connect"))
    )
    (net (code "221") (name "unconnected-(U7-NC-Pad20)") (class "Default")
      (node (ref "U7") (pin "20") (pinfunction "NC_20") (pintype "unspecified+no_connect"))
    )
    (net (code "222") (name "unconnected-(U7-NC-Pad21)") (class "Default")
      (node (ref "U7") (pin "21") (pinfunction "NC_21") (pintype "unspecified+no_connect"))
    )
    (net (code "223") (name "unconnected-(U7-NC-Pad22)") (class "Default")
      (node (ref "U7") (pin "22") (pinfunction "NC_22") (pintype "unspecified+no_connect"))
    )
    (net (code "224") (name "unconnected-(U7-RI-Pad2)") (class "Default")
      (node (ref "U7") (pin "2") (pinfunction "RI_2") (pintype "unspecified+no_connect"))
    )
    (net (code "225") (name "unconnected-(U7-RST#-Pad9)") (class "Default")
      (node (ref "U7") (pin "9") (pinfunction "RST#_9") (pintype "unspecified+no_connect"))
    )
    (net (code "226") (name "unconnected-(U7-SUSPEND#-Pad11)") (class "Default")
      (node (ref "U7") (pin "11") (pinfunction "SUSPEND#_11") (pintype "unspecified+no_connect"))
    )
    (net (code "227") (name "unconnected-(U7-SUSPEND-Pad12)") (class "Default")
      (node (ref "U7") (pin "12") (pinfunction "SUSPEND_12") (pintype "unspecified+no_connect"))
    )
    (net (code "228") (name "unconnected-(U11-Q7S-Pad9)") (class "Default")
      (node (ref "U11") (pin "9") (pinfunction "Q7S_9") (pintype "unspecified+no_connect"))
    )
    (net (code "229") (name "unconnected-(U13-FAULT#-Pad4)") (class "Default")
      (node (ref "U13") (pin "4") (pinfunction "FAULT#_4") (pintype "unspecified+no_connect"))
    )
    (net (code "230") (name "unconnected-(USB1-SBU1-Pad9)") (class "Default")
      (node (ref "USB1") (pin "9") (pinfunction "SBU1_9") (pintype "unspecified+no_connect"))
    )
    (net (code "231") (name "unconnected-(USB1-SBU2-Pad3)") (class "Default")
      (node (ref "USB1") (pin "3") (pinfunction "SBU2_3") (pintype "unspecified+no_connect"))
    )
    (net (code "232") (name "unconnected-(USB2-SBU1-Pad9)") (class "Default")
      (node (ref "USB2") (pin "9") (pinfunction "SBU1_9") (pintype "unspecified+no_connect"))
    )
    (net (code "233") (name "unconnected-(USB2-SBU2-Pad3)") (class "Default")
      (node (ref "USB2") (pin "3") (pinfunction "SBU2_3") (pintype "unspecified+no_connect"))
    )
    (net (code "234") (name "unconnected-(VR1-Pad3)") (class "Default")
      (node (ref "VR1") (pin "3") (pinfunction "3_3") (pintype "unspecified+no_connect"))
    )
  )
)
